# robot.net
KiCad netlist of a schematic drawn in EAGLE
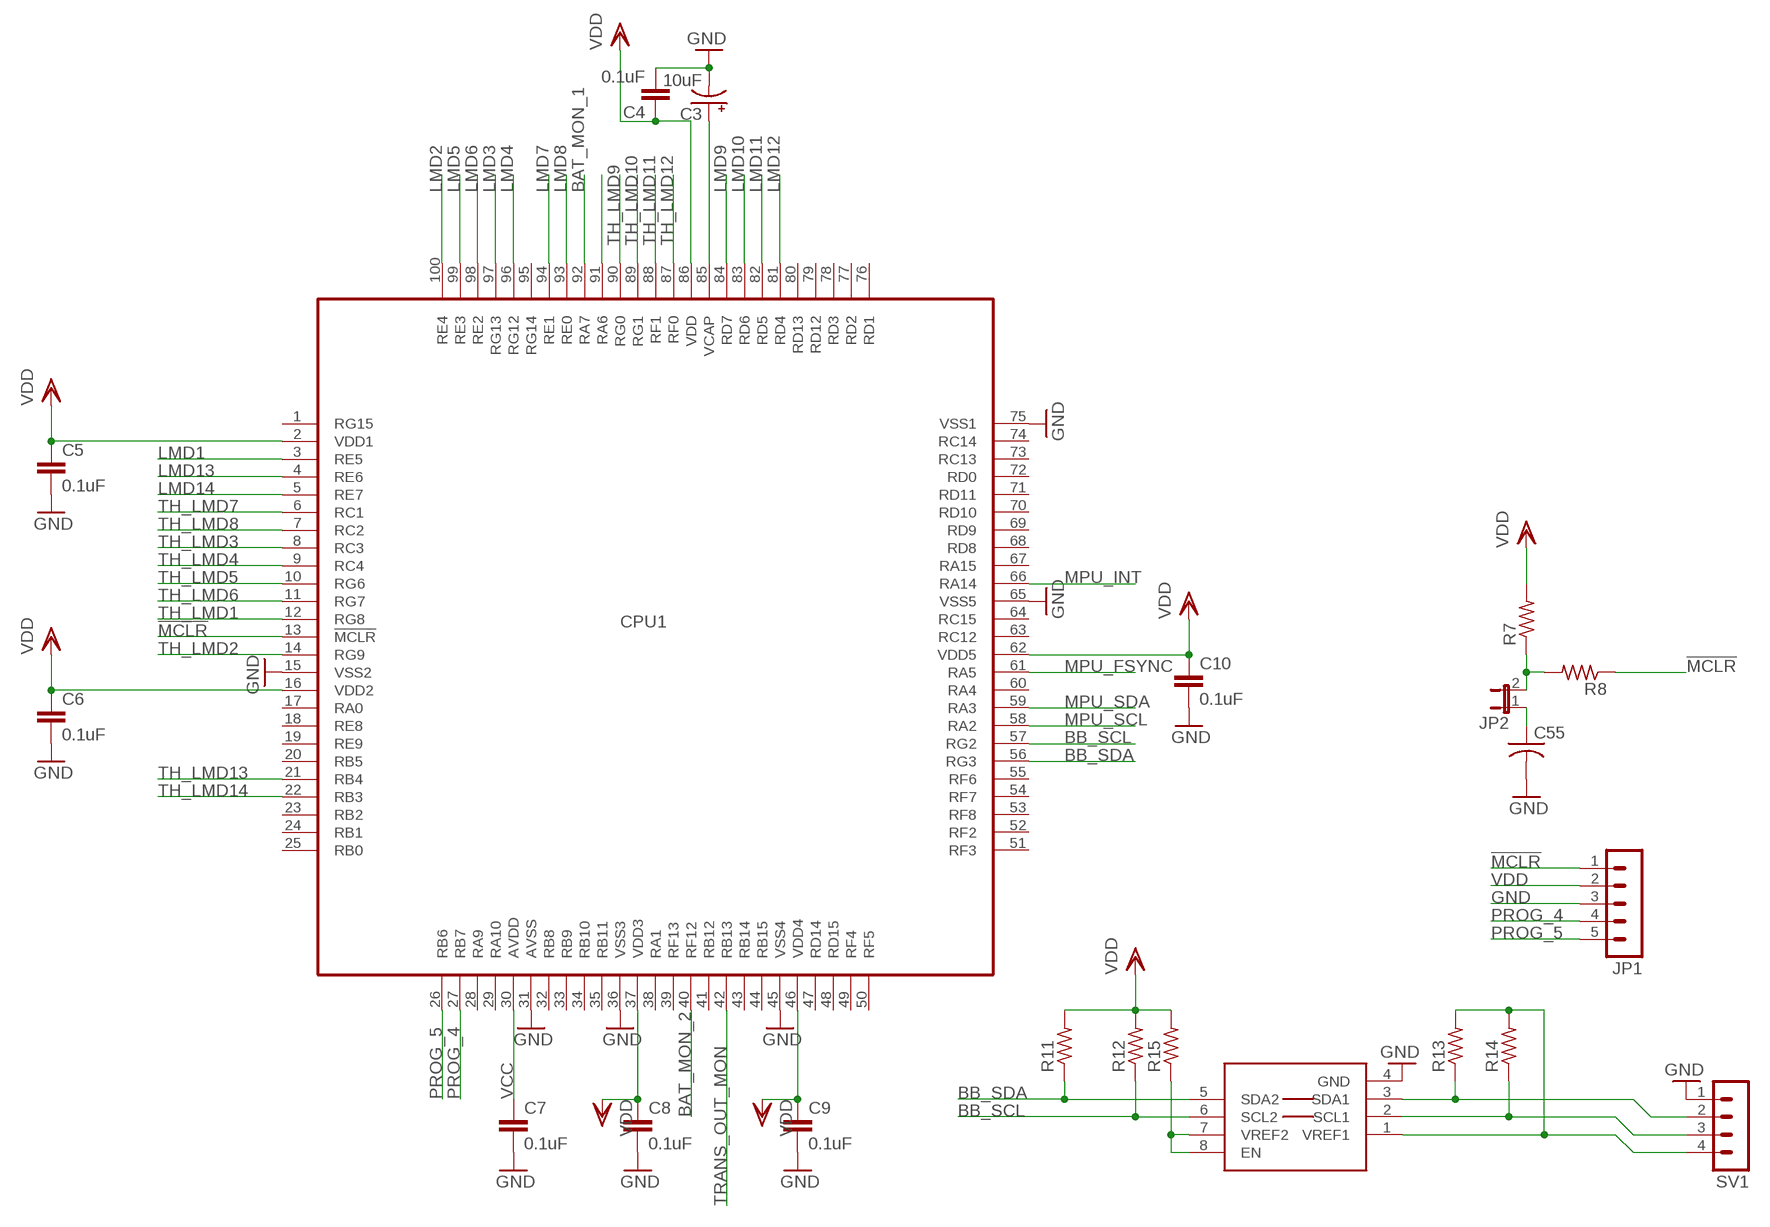
[diagram p0: schematic, sheet 1]
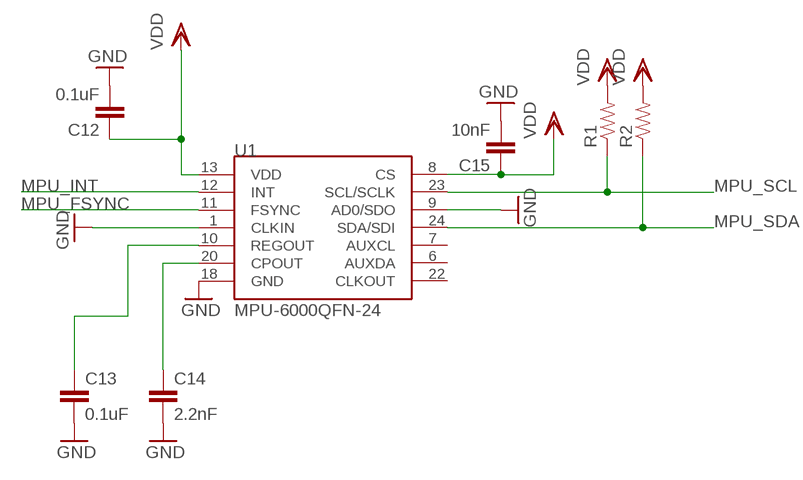
[diagram p1: schematic, sheet 2]
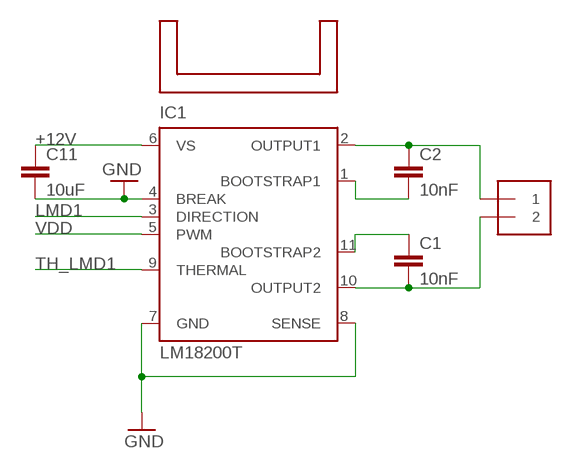
[diagram p2: schematic, sheet 3]
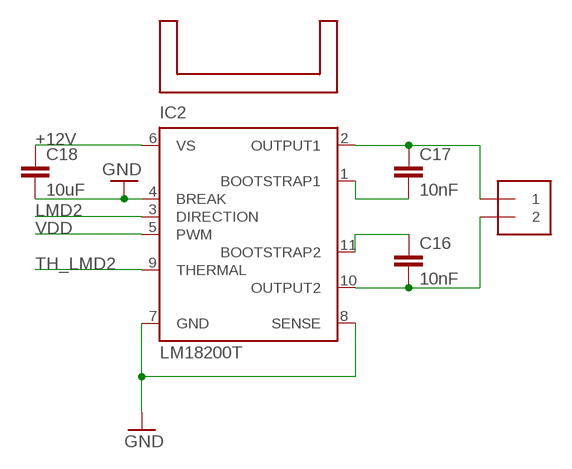
[diagram p3: schematic, sheet 4]
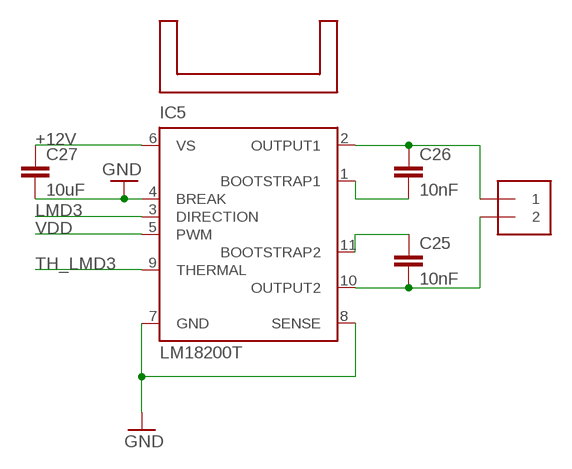
[diagram p4: schematic, sheet 5]
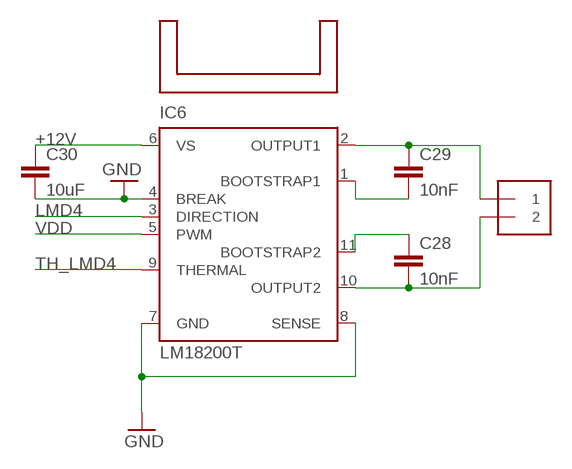
[diagram p5: schematic, sheet 6]
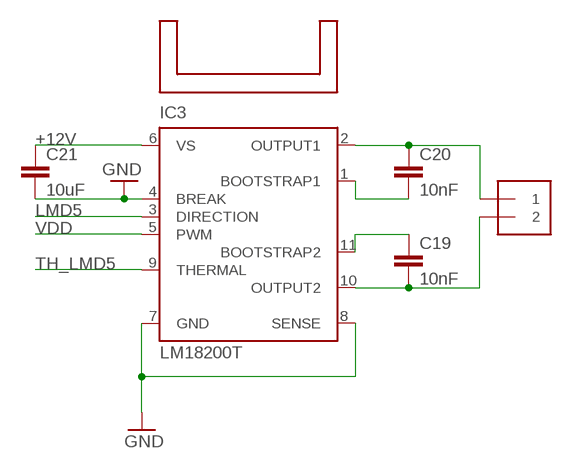
[diagram p6: schematic, sheet 7]
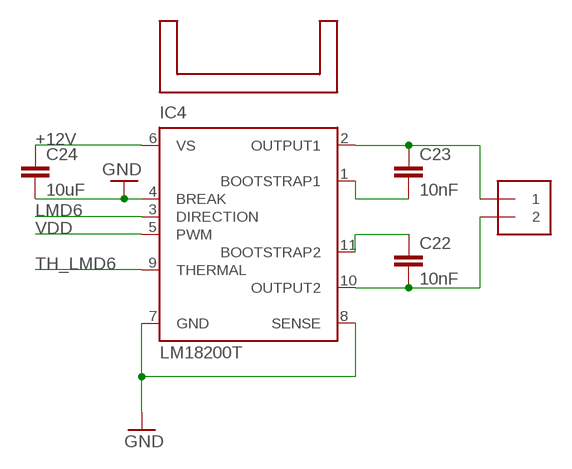
[diagram p7: schematic, sheet 8]
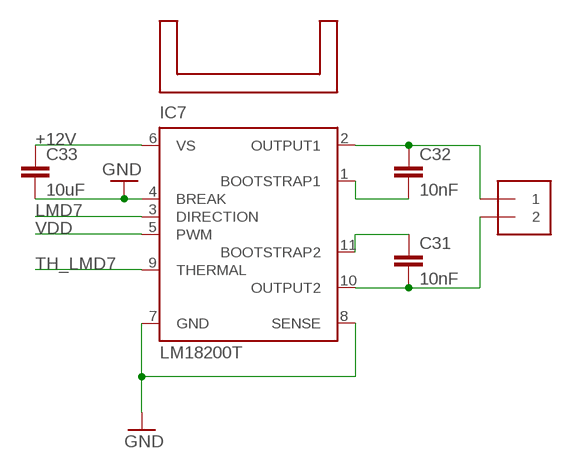
[diagram p8: schematic, sheet 9]
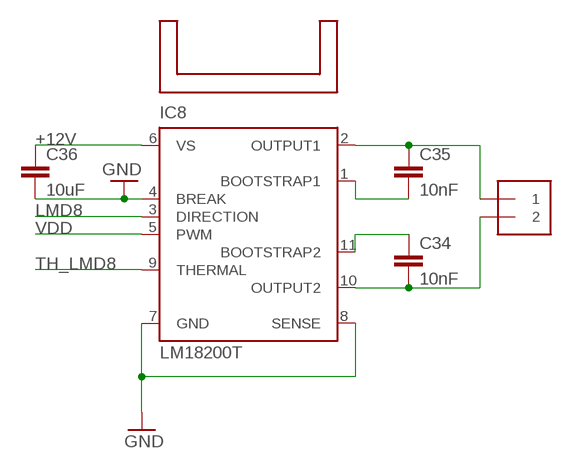
[diagram p9: schematic, sheet 10]
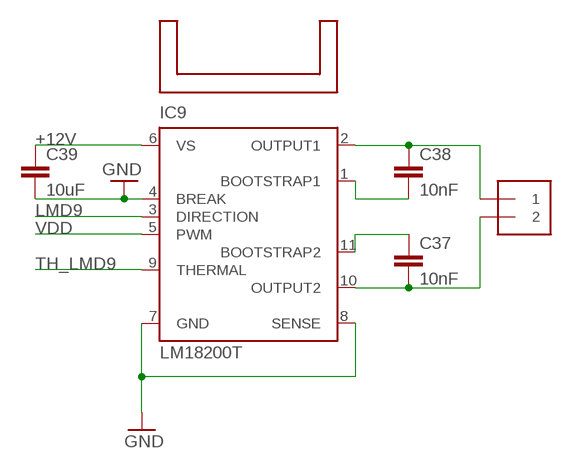
[diagram p10: schematic, sheet 11]
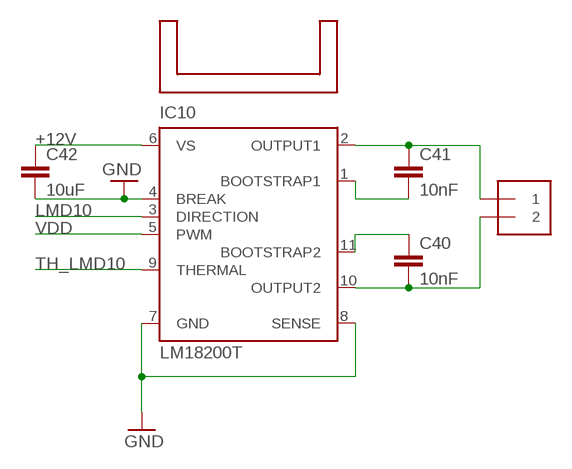
[diagram p11: schematic, sheet 12]
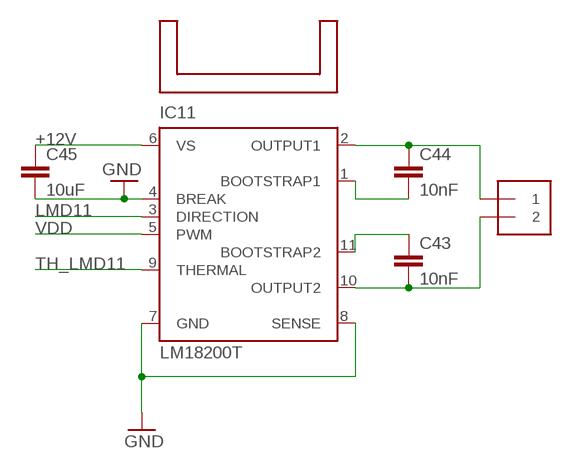
[diagram p12: schematic, sheet 13]
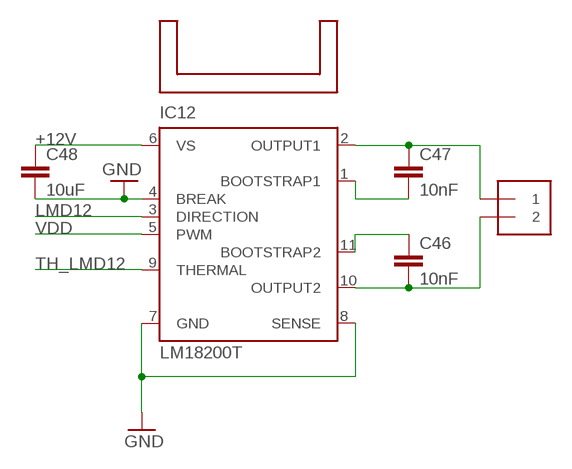
[diagram p13: schematic, sheet 14]
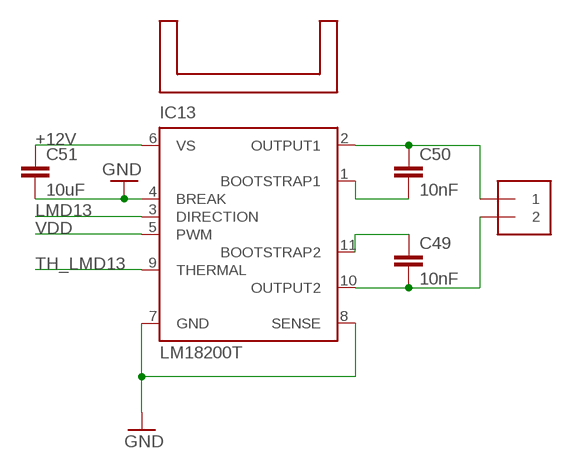
[diagram p14: schematic, sheet 15]
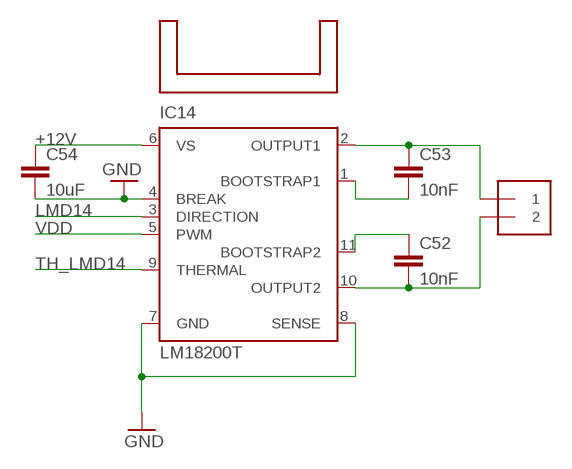
[diagram p15: schematic, sheet 16]
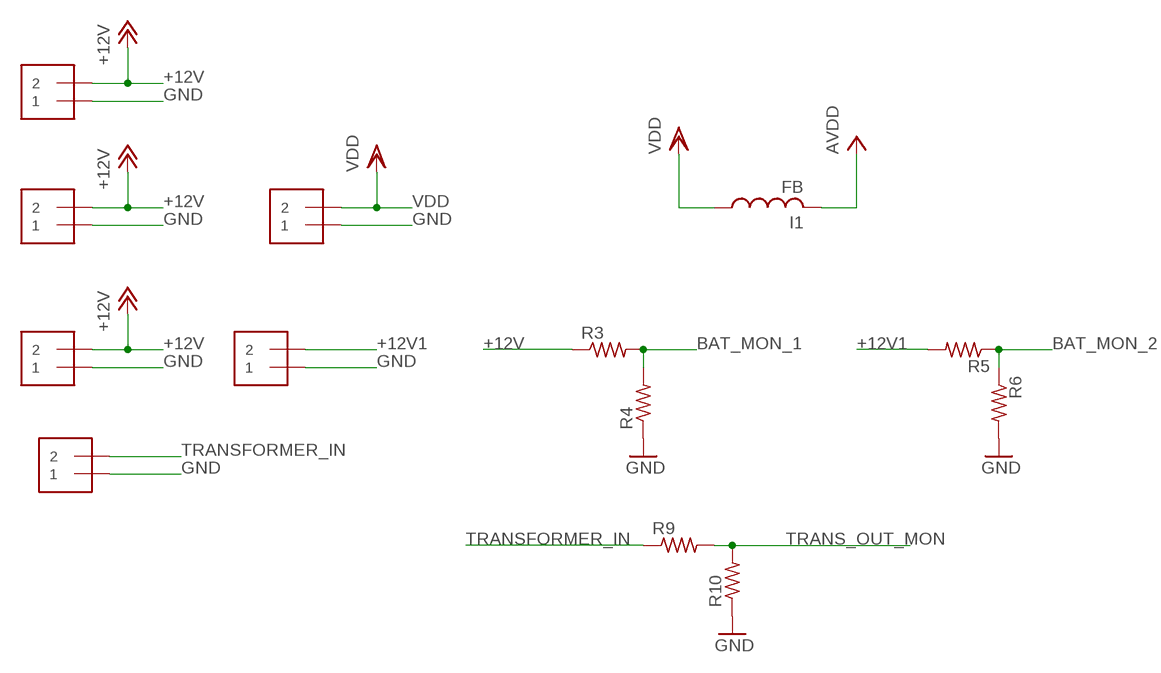
[diagram p16: schematic, sheet 17]

(export (version "E")
  (design (tool "Eeschema 10.0.6"))
  (components
    (comp (ref "C28")
      (value "10nF")
      (footprint "eagle-import:0402-CAP")
      (libsource (lib "eagle-import") (part "10NF-CER"))
    )
    (comp (ref "C29")
      (value "10nF")
      (footprint "eagle-import:0402-CAP")
      (libsource (lib "eagle-import") (part "10NF-CER"))
    )
    (comp (ref "C30")
      (value "10uF")
      (footprint "eagle-import:1206")
      (libsource (lib "eagle-import") (part "10UF-6.3V-20%(1206)"))
    )
    (comp (ref "IC6")
      (value "LM18200T")
      (footprint "eagle-import:TO-220-11")
      (libsource (lib "eagle-import") (part "LM18200T"))
    )
    (comp (ref "J6")
      (value "1X2-3.5MM")
      (footprint "eagle-import:1X2-3.5MM")
      (libsource (lib "eagle-import") (part "1X2-3.5MM"))
    )
    (comp (ref "U$6")
      (value "593002B03400G")
      (footprint "eagle-import:593002B03400G")
      (libsource (lib "eagle-import") (part "593002B03400G"))
    )
    (comp (ref "C12")
      (value "0.1uF")
      (footprint "eagle-import:0402-CAP")
      (libsource (lib "eagle-import") (part "0.1UF-25V(+80/-20%)(0603)"))
    )
    (comp (ref "C13")
      (value "0.1uF")
      (footprint "eagle-import:0402-CAP")
      (libsource (lib "eagle-import") (part "0.1UF-25V(+80/-20%)(0603)"))
    )
    (comp (ref "C14")
      (value "2.2nF")
      (footprint "eagle-import:0402-CAP")
      (libsource (lib "eagle-import") (part "10NF-CER"))
    )
    (comp (ref "C15")
      (value "10nF")
      (footprint "eagle-import:0402-CAP")
      (libsource (lib "eagle-import") (part "10NF-CER"))
    )
    (comp (ref "R1")
      (value "RESISTOR0603-RES")
      (footprint "eagle-import:0603-RES")
      (libsource (lib "eagle-import") (part "RESISTOR0603-RES"))
    )
    (comp (ref "R2")
      (value "RESISTOR0603-RES")
      (footprint "eagle-import:0603-RES")
      (libsource (lib "eagle-import") (part "RESISTOR0603-RES"))
    )
    (comp (ref "U1")
      (value "MPU-6000QFN-24")
      (footprint "eagle-import:QFN-24-TESTING")
      (libsource (lib "eagle-import") (part "MPU-6000QFN-24"))
    )
    (comp (ref "C1")
      (value "10nF")
      (footprint "eagle-import:0402-CAP")
      (libsource (lib "eagle-import") (part "10NF-CER"))
    )
    (comp (ref "C2")
      (value "10nF")
      (footprint "eagle-import:0402-CAP")
      (libsource (lib "eagle-import") (part "10NF-CER"))
    )
    (comp (ref "C11")
      (value "10uF")
      (footprint "eagle-import:1206")
      (libsource (lib "eagle-import") (part "10UF-6.3V-20%(1206)"))
    )
    (comp (ref "IC1")
      (value "LM18200T")
      (footprint "eagle-import:TO-220-11")
      (libsource (lib "eagle-import") (part "LM18200T"))
    )
    (comp (ref "J13")
      (value "1X2-3.5MM")
      (footprint "eagle-import:1X2-3.5MM")
      (libsource (lib "eagle-import") (part "1X2-3.5MM"))
    )
    (comp (ref "U$3")
      (value "593002B03400G")
      (footprint "eagle-import:593002B03400G")
      (libsource (lib "eagle-import") (part "593002B03400G"))
    )
    (comp (ref "C40")
      (value "10nF")
      (footprint "eagle-import:0402-CAP")
      (libsource (lib "eagle-import") (part "10NF-CER"))
    )
    (comp (ref "C41")
      (value "10nF")
      (footprint "eagle-import:0402-CAP")
      (libsource (lib "eagle-import") (part "10NF-CER"))
    )
    (comp (ref "C42")
      (value "10uF")
      (footprint "eagle-import:1206")
      (libsource (lib "eagle-import") (part "10UF-6.3V-20%(1206)"))
    )
    (comp (ref "IC10")
      (value "LM18200T")
      (footprint "eagle-import:TO-220-11")
      (libsource (lib "eagle-import") (part "LM18200T"))
    )
    (comp (ref "J10")
      (value "1X2-3.5MM")
      (footprint "eagle-import:1X2-3.5MM")
      (libsource (lib "eagle-import") (part "1X2-3.5MM"))
    )
    (comp (ref "U$12")
      (value "593002B03400G")
      (footprint "eagle-import:593002B03400G")
      (libsource (lib "eagle-import") (part "593002B03400G"))
    )
    (comp (ref "C22")
      (value "10nF")
      (footprint "eagle-import:0402-CAP")
      (libsource (lib "eagle-import") (part "10NF-CER"))
    )
    (comp (ref "C23")
      (value "10nF")
      (footprint "eagle-import:0402-CAP")
      (libsource (lib "eagle-import") (part "10NF-CER"))
    )
    (comp (ref "C24")
      (value "10uF")
      (footprint "eagle-import:1206")
      (libsource (lib "eagle-import") (part "10UF-6.3V-20%(1206)"))
    )
    (comp (ref "IC4")
      (value "LM18200T")
      (footprint "eagle-import:TO-220-11")
      (libsource (lib "eagle-import") (part "LM18200T"))
    )
    (comp (ref "J4")
      (value "1X2-3.5MM")
      (footprint "eagle-import:1X2-3.5MM")
      (libsource (lib "eagle-import") (part "1X2-3.5MM"))
    )
    (comp (ref "U$8")
      (value "593002B03400G")
      (footprint "eagle-import:593002B03400G")
      (libsource (lib "eagle-import") (part "593002B03400G"))
    )
    (comp (ref "C49")
      (value "10nF")
      (footprint "eagle-import:0402-CAP")
      (libsource (lib "eagle-import") (part "10NF-CER"))
    )
    (comp (ref "C50")
      (value "10nF")
      (footprint "eagle-import:0402-CAP")
      (libsource (lib "eagle-import") (part "10NF-CER"))
    )
    (comp (ref "C51")
      (value "10uF")
      (footprint "eagle-import:1206")
      (libsource (lib "eagle-import") (part "10UF-6.3V-20%(1206)"))
    )
    (comp (ref "IC13")
      (value "LM18200T")
      (footprint "eagle-import:TO-220-11")
      (libsource (lib "eagle-import") (part "LM18200T"))
    )
    (comp (ref "J15")
      (value "1X2-3.5MM")
      (footprint "eagle-import:1X2-3.5MM")
      (libsource (lib "eagle-import") (part "1X2-3.5MM"))
    )
    (comp (ref "U$15")
      (value "593002B03400G")
      (footprint "eagle-import:593002B03400G")
      (libsource (lib "eagle-import") (part "593002B03400G"))
    )
    (comp (ref "C19")
      (value "10nF")
      (footprint "eagle-import:0402-CAP")
      (libsource (lib "eagle-import") (part "10NF-CER"))
    )
    (comp (ref "C20")
      (value "10nF")
      (footprint "eagle-import:0402-CAP")
      (libsource (lib "eagle-import") (part "10NF-CER"))
    )
    (comp (ref "C21")
      (value "10uF")
      (footprint "eagle-import:1206")
      (libsource (lib "eagle-import") (part "10UF-6.3V-20%(1206)"))
    )
    (comp (ref "IC3")
      (value "LM18200T")
      (footprint "eagle-import:TO-220-11")
      (libsource (lib "eagle-import") (part "LM18200T"))
    )
    (comp (ref "J3")
      (value "1X2-3.5MM")
      (footprint "eagle-import:1X2-3.5MM")
      (libsource (lib "eagle-import") (part "1X2-3.5MM"))
    )
    (comp (ref "U$7")
      (value "593002B03400G")
      (footprint "eagle-import:593002B03400G")
      (libsource (lib "eagle-import") (part "593002B03400G"))
    )
    (comp (ref "C31")
      (value "10nF")
      (footprint "eagle-import:0402-CAP")
      (libsource (lib "eagle-import") (part "10NF-CER"))
    )
    (comp (ref "C32")
      (value "10nF")
      (footprint "eagle-import:0402-CAP")
      (libsource (lib "eagle-import") (part "10NF-CER"))
    )
    (comp (ref "C33")
      (value "10uF")
      (footprint "eagle-import:1206")
      (libsource (lib "eagle-import") (part "10UF-6.3V-20%(1206)"))
    )
    (comp (ref "IC7")
      (value "LM18200T")
      (footprint "eagle-import:TO-220-11")
      (libsource (lib "eagle-import") (part "LM18200T"))
    )
    (comp (ref "J7")
      (value "1X2-3.5MM")
      (footprint "eagle-import:1X2-3.5MM")
      (libsource (lib "eagle-import") (part "1X2-3.5MM"))
    )
    (comp (ref "U$9")
      (value "593002B03400G")
      (footprint "eagle-import:593002B03400G")
      (libsource (lib "eagle-import") (part "593002B03400G"))
    )
    (comp (ref "C25")
      (value "10nF")
      (footprint "eagle-import:0402-CAP")
      (libsource (lib "eagle-import") (part "10NF-CER"))
    )
    (comp (ref "C26")
      (value "10nF")
      (footprint "eagle-import:0402-CAP")
      (libsource (lib "eagle-import") (part "10NF-CER"))
    )
    (comp (ref "C27")
      (value "10uF")
      (footprint "eagle-import:1206")
      (libsource (lib "eagle-import") (part "10UF-6.3V-20%(1206)"))
    )
    (comp (ref "IC5")
      (value "LM18200T")
      (footprint "eagle-import:TO-220-11")
      (libsource (lib "eagle-import") (part "LM18200T"))
    )
    (comp (ref "J5")
      (value "1X2-3.5MM")
      (footprint "eagle-import:1X2-3.5MM")
      (libsource (lib "eagle-import") (part "1X2-3.5MM"))
    )
    (comp (ref "U$5")
      (value "593002B03400G")
      (footprint "eagle-import:593002B03400G")
      (libsource (lib "eagle-import") (part "593002B03400G"))
    )
    (comp (ref "C16")
      (value "10nF")
      (footprint "eagle-import:0402-CAP")
      (libsource (lib "eagle-import") (part "10NF-CER"))
    )
    (comp (ref "C17")
      (value "10nF")
      (footprint "eagle-import:0402-CAP")
      (libsource (lib "eagle-import") (part "10NF-CER"))
    )
    (comp (ref "C18")
      (value "10uF")
      (footprint "eagle-import:1206")
      (libsource (lib "eagle-import") (part "10UF-6.3V-20%(1206)"))
    )
    (comp (ref "IC2")
      (value "LM18200T")
      (footprint "eagle-import:TO-220-11")
      (libsource (lib "eagle-import") (part "LM18200T"))
    )
    (comp (ref "J2")
      (value "1X2-3.5MM")
      (footprint "eagle-import:1X2-3.5MM")
      (libsource (lib "eagle-import") (part "1X2-3.5MM"))
    )
    (comp (ref "U$4")
      (value "593002B03400G")
      (footprint "eagle-import:593002B03400G")
      (libsource (lib "eagle-import") (part "593002B03400G"))
    )
    (comp (ref "C37")
      (value "10nF")
      (footprint "eagle-import:0402-CAP")
      (libsource (lib "eagle-import") (part "10NF-CER"))
    )
    (comp (ref "C38")
      (value "10nF")
      (footprint "eagle-import:0402-CAP")
      (libsource (lib "eagle-import") (part "10NF-CER"))
    )
    (comp (ref "C39")
      (value "10uF")
      (footprint "eagle-import:1206")
      (libsource (lib "eagle-import") (part "10UF-6.3V-20%(1206)"))
    )
    (comp (ref "IC9")
      (value "LM18200T")
      (footprint "eagle-import:TO-220-11")
      (libsource (lib "eagle-import") (part "LM18200T"))
    )
    (comp (ref "J9")
      (value "1X2-3.5MM")
      (footprint "eagle-import:1X2-3.5MM")
      (libsource (lib "eagle-import") (part "1X2-3.5MM"))
    )
    (comp (ref "U$11")
      (value "593002B03400G")
      (footprint "eagle-import:593002B03400G")
      (libsource (lib "eagle-import") (part "593002B03400G"))
    )
    (comp (ref "C52")
      (value "10nF")
      (footprint "eagle-import:0402-CAP")
      (libsource (lib "eagle-import") (part "10NF-CER"))
    )
    (comp (ref "C53")
      (value "10nF")
      (footprint "eagle-import:0402-CAP")
      (libsource (lib "eagle-import") (part "10NF-CER"))
    )
    (comp (ref "C54")
      (value "10uF")
      (footprint "eagle-import:1206")
      (libsource (lib "eagle-import") (part "10UF-6.3V-20%(1206)"))
    )
    (comp (ref "IC14")
      (value "LM18200T")
      (footprint "eagle-import:TO-220-11")
      (libsource (lib "eagle-import") (part "LM18200T"))
    )
    (comp (ref "J16")
      (value "1X2-3.5MM")
      (footprint "eagle-import:1X2-3.5MM")
      (libsource (lib "eagle-import") (part "1X2-3.5MM"))
    )
    (comp (ref "U$16")
      (value "593002B03400G")
      (footprint "eagle-import:593002B03400G")
      (libsource (lib "eagle-import") (part "593002B03400G"))
    )
    (comp (ref "I1") (value "FB") (footprint "eagle-import:FB") (libsource (lib "eagle-import") (part "FB")))
    (comp (ref "J1")
      (value "1X2-3.5MM")
      (footprint "eagle-import:1X2-3.5MM")
      (libsource (lib "eagle-import") (part "1X2-3.5MM"))
    )
    (comp (ref "J12")
      (value "1X2-3.5MM")
      (footprint "eagle-import:1X2-3.5MM")
      (libsource (lib "eagle-import") (part "1X2-3.5MM"))
    )
    (comp (ref "J17")
      (value "1X2-3.5MM")
      (footprint "eagle-import:1X2-3.5MM")
      (libsource (lib "eagle-import") (part "1X2-3.5MM"))
    )
    (comp (ref "J18")
      (value "1X2-3.5MM")
      (footprint "eagle-import:1X2-3.5MM")
      (libsource (lib "eagle-import") (part "1X2-3.5MM"))
    )
    (comp (ref "J19")
      (value "1X2-3.5MM")
      (footprint "eagle-import:1X2-3.5MM")
      (libsource (lib "eagle-import") (part "1X2-3.5MM"))
    )
    (comp (ref "J20")
      (value "1X2-3.5MM")
      (footprint "eagle-import:1X2-3.5MM")
      (libsource (lib "eagle-import") (part "1X2-3.5MM"))
    )
    (comp (ref "R3")
      (value "R-US_R0603")
      (footprint "eagle-import:R0603")
      (libsource (lib "eagle-import") (part "R-US_R0603"))
    )
    (comp (ref "R4")
      (value "R-US_R0603")
      (footprint "eagle-import:R0603")
      (libsource (lib "eagle-import") (part "R-US_R0603"))
    )
    (comp (ref "R5")
      (value "R-US_R0603")
      (footprint "eagle-import:R0603")
      (libsource (lib "eagle-import") (part "R-US_R0603"))
    )
    (comp (ref "R6")
      (value "R-US_R0603")
      (footprint "eagle-import:R0603")
      (libsource (lib "eagle-import") (part "R-US_R0603"))
    )
    (comp (ref "R9")
      (value "R-US_R0603")
      (footprint "eagle-import:R0603")
      (libsource (lib "eagle-import") (part "R-US_R0603"))
    )
    (comp (ref "R10")
      (value "R-US_R0603")
      (footprint "eagle-import:R0603")
      (libsource (lib "eagle-import") (part "R-US_R0603"))
    )
    (comp (ref "C43")
      (value "10nF")
      (footprint "eagle-import:0402-CAP")
      (libsource (lib "eagle-import") (part "10NF-CER"))
    )
    (comp (ref "C44")
      (value "10nF")
      (footprint "eagle-import:0402-CAP")
      (libsource (lib "eagle-import") (part "10NF-CER"))
    )
    (comp (ref "C45")
      (value "10uF")
      (footprint "eagle-import:1206")
      (libsource (lib "eagle-import") (part "10UF-6.3V-20%(1206)"))
    )
    (comp (ref "IC11")
      (value "LM18200T")
      (footprint "eagle-import:TO-220-11")
      (libsource (lib "eagle-import") (part "LM18200T"))
    )
    (comp (ref "J11")
      (value "1X2-3.5MM")
      (footprint "eagle-import:1X2-3.5MM")
      (libsource (lib "eagle-import") (part "1X2-3.5MM"))
    )
    (comp (ref "U$13")
      (value "593002B03400G")
      (footprint "eagle-import:593002B03400G")
      (libsource (lib "eagle-import") (part "593002B03400G"))
    )
    (comp (ref "C34")
      (value "10nF")
      (footprint "eagle-import:0402-CAP")
      (libsource (lib "eagle-import") (part "10NF-CER"))
    )
    (comp (ref "C35")
      (value "10nF")
      (footprint "eagle-import:0402-CAP")
      (libsource (lib "eagle-import") (part "10NF-CER"))
    )
    (comp (ref "C36")
      (value "10uF")
      (footprint "eagle-import:1206")
      (libsource (lib "eagle-import") (part "10UF-6.3V-20%(1206)"))
    )
    (comp (ref "IC8")
      (value "LM18200T")
      (footprint "eagle-import:TO-220-11")
      (libsource (lib "eagle-import") (part "LM18200T"))
    )
    (comp (ref "J8")
      (value "1X2-3.5MM")
      (footprint "eagle-import:1X2-3.5MM")
      (libsource (lib "eagle-import") (part "1X2-3.5MM"))
    )
    (comp (ref "U$10")
      (value "593002B03400G")
      (footprint "eagle-import:593002B03400G")
      (libsource (lib "eagle-import") (part "593002B03400G"))
    )
    (comp (ref "C46")
      (value "10nF")
      (footprint "eagle-import:0402-CAP")
      (libsource (lib "eagle-import") (part "10NF-CER"))
    )
    (comp (ref "C47")
      (value "10nF")
      (footprint "eagle-import:0402-CAP")
      (libsource (lib "eagle-import") (part "10NF-CER"))
    )
    (comp (ref "C48")
      (value "10uF")
      (footprint "eagle-import:1206")
      (libsource (lib "eagle-import") (part "10UF-6.3V-20%(1206)"))
    )
    (comp (ref "IC12")
      (value "LM18200T")
      (footprint "eagle-import:TO-220-11")
      (libsource (lib "eagle-import") (part "LM18200T"))
    )
    (comp (ref "J14")
      (value "1X2-3.5MM")
      (footprint "eagle-import:1X2-3.5MM")
      (libsource (lib "eagle-import") (part "1X2-3.5MM"))
    )
    (comp (ref "U$14")
      (value "593002B03400G")
      (footprint "eagle-import:593002B03400G")
      (libsource (lib "eagle-import") (part "593002B03400G"))
    )
    (comp (ref "C3")
      (value "10uF")
      (footprint "eagle-import:EIA3216")
      (libsource (lib "eagle-import") (part "10UF-TANT"))
    )
    (comp (ref "C4")
      (value "0.1uF")
      (footprint "eagle-import:0402-CAP")
      (libsource (lib "eagle-import") (part "0.1UF-25V(+80/-20%)(0603)"))
    )
    (comp (ref "C5")
      (value "0.1uF")
      (footprint "eagle-import:0402-CAP")
      (libsource (lib "eagle-import") (part "0.1UF-25V(+80/-20%)(0603)"))
    )
    (comp (ref "C6")
      (value "0.1uF")
      (footprint "eagle-import:0402-CAP")
      (libsource (lib "eagle-import") (part "0.1UF-25V(+80/-20%)(0603)"))
    )
    (comp (ref "C7")
      (value "0.1uF")
      (footprint "eagle-import:0402-CAP")
      (libsource (lib "eagle-import") (part "0.1UF-25V(+80/-20%)(0603)"))
    )
    (comp (ref "C8")
      (value "0.1uF")
      (footprint "eagle-import:0402-CAP")
      (libsource (lib "eagle-import") (part "0.1UF-25V(+80/-20%)(0603)"))
    )
    (comp (ref "C9")
      (value "0.1uF")
      (footprint "eagle-import:0402-CAP")
      (libsource (lib "eagle-import") (part "0.1UF-25V(+80/-20%)(0603)"))
    )
    (comp (ref "C10")
      (value "0.1uF")
      (footprint "eagle-import:0402-CAP")
      (libsource (lib "eagle-import") (part "0.1UF-25V(+80/-20%)(0603)"))
    )
    (comp (ref "C55")
      (value "C-USC0603")
      (footprint "eagle-import:C0603")
      (libsource (lib "eagle-import") (part "C-USC0603"))
    )
    (comp (ref "CPU1")
      (value "DSPIC33FJ32GS610TQFP")
      (footprint "eagle-import:TQFP100-14X14")
      (libsource (lib "eagle-import") (part "DSPIC33FJ32GS610TQFP"))
    )
    (comp (ref "JP1")
      (value "MA05-1")
      (footprint "eagle-import:MA05-1")
      (libsource (lib "eagle-import") (part "MA05-1"))
    )
    (comp (ref "JP2")
      (value "JP1E")
      (footprint "eagle-import:JP1")
      (libsource (lib "eagle-import") (part "JP1E"))
    )
    (comp (ref "R7")
      (value "R-US_R0603")
      (footprint "eagle-import:R0603")
      (libsource (lib "eagle-import") (part "R-US_R0603"))
    )
    (comp (ref "R8")
      (value "R-US_R0603")
      (footprint "eagle-import:R0603")
      (libsource (lib "eagle-import") (part "R-US_R0603"))
    )
    (comp (ref "R11")
      (value "R-US_R0603")
      (footprint "eagle-import:R0603")
      (libsource (lib "eagle-import") (part "R-US_R0603"))
    )
    (comp (ref "R12")
      (value "R-US_R0603")
      (footprint "eagle-import:R0603")
      (libsource (lib "eagle-import") (part "R-US_R0603"))
    )
    (comp (ref "R13")
      (value "R-US_R0603")
      (footprint "eagle-import:R0603")
      (libsource (lib "eagle-import") (part "R-US_R0603"))
    )
    (comp (ref "R14")
      (value "R-US_R0603")
      (footprint "eagle-import:R0603")
      (libsource (lib "eagle-import") (part "R-US_R0603"))
    )
    (comp (ref "R15")
      (value "R-US_R0603")
      (footprint "eagle-import:R0603")
      (libsource (lib "eagle-import") (part "R-US_R0603"))
    )
    (comp (ref "SV1")
      (value "MA04-1")
      (footprint "eagle-import:MA04-1")
      (libsource (lib "eagle-import") (part "MA04-1"))
    )
    (comp (ref "U$17")
      (value "PCA9306")
      (footprint "eagle-import:PSOP-8")
      (libsource (lib "eagle-import") (part "PCA9306"))
    )
  )
  (nets
    (net (code "1") (name "+12V") (class "Default")
      (node (ref "C11") (pin "1") (pinfunction "1_1") (pintype "passive"))
      (node (ref "C18") (pin "1") (pinfunction "1_1") (pintype "passive"))
      (node (ref "C21") (pin "1") (pinfunction "1_1") (pintype "passive"))
      (node (ref "C24") (pin "1") (pinfunction "1_1") (pintype "passive"))
      (node (ref "C27") (pin "1") (pinfunction "1_1") (pintype "passive"))
      (node (ref "C30") (pin "1") (pinfunction "1_1") (pintype "passive"))
      (node (ref "C33") (pin "1") (pinfunction "1_1") (pintype "passive"))
      (node (ref "C36") (pin "1") (pinfunction "1_1") (pintype "passive"))
      (node (ref "C39") (pin "1") (pinfunction "1_1") (pintype "passive"))
      (node (ref "C42") (pin "1") (pinfunction "1_1") (pintype "passive"))
      (node (ref "C45") (pin "1") (pinfunction "1_1") (pintype "passive"))
      (node (ref "C48") (pin "1") (pinfunction "1_1") (pintype "passive"))
      (node (ref "C51") (pin "1") (pinfunction "1_1") (pintype "passive"))
      (node (ref "C54") (pin "1") (pinfunction "1_1") (pintype "passive"))
      (node (ref "IC1") (pin "6") (pinfunction "VS_6") (pintype "power_in"))
      (node (ref "IC10") (pin "6") (pinfunction "VS_6") (pintype "power_in"))
      (node (ref "IC11") (pin "6") (pinfunction "VS_6") (pintype "power_in"))
      (node (ref "IC12") (pin "6") (pinfunction "VS_6") (pintype "power_in"))
      (node (ref "IC13") (pin "6") (pinfunction "VS_6") (pintype "power_in"))
      (node (ref "IC14") (pin "6") (pinfunction "VS_6") (pintype "power_in"))
      (node (ref "IC2") (pin "6") (pinfunction "VS_6") (pintype "power_in"))
      (node (ref "IC3") (pin "6") (pinfunction "VS_6") (pintype "power_in"))
      (node (ref "IC4") (pin "6") (pinfunction "VS_6") (pintype "power_in"))
      (node (ref "IC5") (pin "6") (pinfunction "VS_6") (pintype "power_in"))
      (node (ref "IC6") (pin "6") (pinfunction "VS_6") (pintype "power_in"))
      (node (ref "IC7") (pin "6") (pinfunction "VS_6") (pintype "power_in"))
      (node (ref "IC8") (pin "6") (pinfunction "VS_6") (pintype "power_in"))
      (node (ref "IC9") (pin "6") (pinfunction "VS_6") (pintype "power_in"))
      (node (ref "J12") (pin "2") (pinfunction "2_2") (pintype "passive"))
      (node (ref "J17") (pin "2") (pinfunction "2_2") (pintype "passive"))
      (node (ref "J20") (pin "2") (pinfunction "2_2") (pintype "passive"))
      (node (ref "R3") (pin "1") (pinfunction "1_1") (pintype "passive"))
    )
    (net (code "2") (name "+12V1") (class "Default")
      (node (ref "J18") (pin "2") (pinfunction "2_2") (pintype "passive"))
      (node (ref "R5") (pin "2") (pinfunction "2_2") (pintype "passive"))
    )
    (net (code "3") (name "BAT_MON_1") (class "Default")
      (node (ref "CPU1") (pin "92") (pinfunction "RA7_92") (pintype "bidirectional"))
      (node (ref "R3") (pin "2") (pinfunction "2_2") (pintype "passive"))
      (node (ref "R4") (pin "2") (pinfunction "2_2") (pintype "passive"))
    )
    (net (code "4") (name "BAT_MON_2") (class "Default")
      (node (ref "CPU1") (pin "40") (pinfunction "RF12_40") (pintype "bidirectional"))
      (node (ref "R5") (pin "1") (pinfunction "1_1") (pintype "passive"))
      (node (ref "R6") (pin "1") (pinfunction "1_1") (pintype "passive"))
    )
    (net (code "5") (name "BB_SCL") (class "Default")
      (node (ref "CPU1") (pin "57") (pinfunction "RG2_57") (pintype "bidirectional"))
      (node (ref "R12") (pin "1") (pinfunction "1_1") (pintype "passive"))
      (node (ref "U$17") (pin "6") (pinfunction "SCL2_6") (pintype "bidirectional"))
    )
    (net (code "6") (name "BB_SDA") (class "Default")
      (node (ref "CPU1") (pin "56") (pinfunction "RG3_56") (pintype "bidirectional"))
      (node (ref "R11") (pin "1") (pinfunction "1_1") (pintype "passive"))
      (node (ref "U$17") (pin "5") (pinfunction "SDA2_5") (pintype "bidirectional"))
    )
    (net (code "7") (name "GND") (class "Default")
      (node (ref "C10") (pin "2") (pinfunction "2_2") (pintype "passive"))
      (node (ref "C11") (pin "2") (pinfunction "2_2") (pintype "passive"))
      (node (ref "C12") (pin "2") (pinfunction "2_2") (pintype "passive"))
      (node (ref "C13") (pin "2") (pinfunction "2_2") (pintype "passive"))
      (node (ref "C14") (pin "2") (pinfunction "2_2") (pintype "passive"))
      (node (ref "C15") (pin "2") (pinfunction "2_2") (pintype "passive"))
      (node (ref "C18") (pin "2") (pinfunction "2_2") (pintype "passive"))
      (node (ref "C21") (pin "2") (pinfunction "2_2") (pintype "passive"))
      (node (ref "C24") (pin "2") (pinfunction "2_2") (pintype "passive"))
      (node (ref "C27") (pin "2") (pinfunction "2_2") (pintype "passive"))
      (node (ref "C3") (pin "C") (pinfunction "-_C") (pintype "passive"))
      (node (ref "C30") (pin "2") (pinfunction "2_2") (pintype "passive"))
      (node (ref "C33") (pin "2") (pinfunction "2_2") (pintype "passive"))
      (node (ref "C36") (pin "2") (pinfunction "2_2") (pintype "passive"))
      (node (ref "C39") (pin "2") (pinfunction "2_2") (pintype "passive"))
      (node (ref "C4") (pin "2") (pinfunction "2_2") (pintype "passive"))
      (node (ref "C42") (pin "2") (pinfunction "2_2") (pintype "passive"))
      (node (ref "C45") (pin "2") (pinfunction "2_2") (pintype "passive"))
      (node (ref "C48") (pin "2") (pinfunction "2_2") (pintype "passive"))
      (node (ref "C5") (pin "2") (pinfunction "2_2") (pintype "passive"))
      (node (ref "C51") (pin "2") (pinfunction "2_2") (pintype "passive"))
      (node (ref "C54") (pin "2") (pinfunction "2_2") (pintype "passive"))
      (node (ref "C55") (pin "2") (pinfunction "2_2") (pintype "passive"))
      (node (ref "C6") (pin "2") (pinfunction "2_2") (pintype "passive"))
      (node (ref "C7") (pin "2") (pinfunction "2_2") (pintype "passive"))
      (node (ref "C8") (pin "2") (pinfunction "2_2") (pintype "passive"))
      (node (ref "C9") (pin "2") (pinfunction "2_2") (pintype "passive"))
      (node (ref "CPU1") (pin "15") (pinfunction "VSS2_15") (pintype "power_in"))
      (node (ref "CPU1") (pin "31") (pinfunction "AVSS_31") (pintype "power_in"))
      (node (ref "CPU1") (pin "36") (pinfunction "VSS3_36") (pintype "power_in"))
      (node (ref "CPU1") (pin "45") (pinfunction "VSS4_45") (pintype "power_in"))
      (node (ref "CPU1") (pin "65") (pinfunction "VSS5_65") (pintype "power_in"))
      (node (ref "CPU1") (pin "75") (pinfunction "VSS1_75") (pintype "power_in"))
      (node (ref "IC1") (pin "4") (pinfunction "BREAK_4") (pintype "input"))
      (node (ref "IC1") (pin "7") (pinfunction "GND_7") (pintype "power_in"))
      (node (ref "IC1") (pin "8") (pinfunction "SENSE_8") (pintype "output"))
      (node (ref "IC10") (pin "4") (pinfunction "BREAK_4") (pintype "input"))
      (node (ref "IC10") (pin "7") (pinfunction "GND_7") (pintype "power_in"))
      (node (ref "IC10") (pin "8") (pinfunction "SENSE_8") (pintype "output"))
      (node (ref "IC11") (pin "4") (pinfunction "BREAK_4") (pintype "input"))
      (node (ref "IC11") (pin "7") (pinfunction "GND_7") (pintype "power_in"))
      (node (ref "IC11") (pin "8") (pinfunction "SENSE_8") (pintype "output"))
      (node (ref "IC12") (pin "4") (pinfunction "BREAK_4") (pintype "input"))
      (node (ref "IC12") (pin "7") (pinfunction "GND_7") (pintype "power_in"))
      (node (ref "IC12") (pin "8") (pinfunction "SENSE_8") (pintype "output"))
      (node (ref "IC13") (pin "4") (pinfunction "BREAK_4") (pintype "input"))
      (node (ref "IC13") (pin "7") (pinfunction "GND_7") (pintype "power_in"))
      (node (ref "IC13") (pin "8") (pinfunction "SENSE_8") (pintype "output"))
      (node (ref "IC14") (pin "4") (pinfunction "BREAK_4") (pintype "input"))
      (node (ref "IC14") (pin "7") (pinfunction "GND_7") (pintype "power_in"))
      (node (ref "IC14") (pin "8") (pinfunction "SENSE_8") (pintype "output"))
      (node (ref "IC2") (pin "4") (pinfunction "BREAK_4") (pintype "input"))
      (node (ref "IC2") (pin "7") (pinfunction "GND_7") (pintype "power_in"))
      (node (ref "IC2") (pin "8") (pinfunction "SENSE_8") (pintype "output"))
      (node (ref "IC3") (pin "4") (pinfunction "BREAK_4") (pintype "input"))
      (node (ref "IC3") (pin "7") (pinfunction "GND_7") (pintype "power_in"))
      (node (ref "IC3") (pin "8") (pinfunction "SENSE_8") (pintype "output"))
      (node (ref "IC4") (pin "4") (pinfunction "BREAK_4") (pintype "input"))
      (node (ref "IC4") (pin "7") (pinfunction "GND_7") (pintype "power_in"))
      (node (ref "IC4") (pin "8") (pinfunction "SENSE_8") (pintype "output"))
      (node (ref "IC5") (pin "4") (pinfunction "BREAK_4") (pintype "input"))
      (node (ref "IC5") (pin "7") (pinfunction "GND_7") (pintype "power_in"))
      (node (ref "IC5") (pin "8") (pinfunction "SENSE_8") (pintype "output"))
      (node (ref "IC6") (pin "4") (pinfunction "BREAK_4") (pintype "input"))
      (node (ref "IC6") (pin "7") (pinfunction "GND_7") (pintype "power_in"))
      (node (ref "IC6") (pin "8") (pinfunction "SENSE_8") (pintype "output"))
      (node (ref "IC7") (pin "4") (pinfunction "BREAK_4") (pintype "input"))
      (node (ref "IC7") (pin "7") (pinfunction "GND_7") (pintype "power_in"))
      (node (ref "IC7") (pin "8") (pinfunction "SENSE_8") (pintype "output"))
      (node (ref "IC8") (pin "4") (pinfunction "BREAK_4") (pintype "input"))
      (node (ref "IC8") (pin "7") (pinfunction "GND_7") (pintype "power_in"))
      (node (ref "IC8") (pin "8") (pinfunction "SENSE_8") (pintype "output"))
      (node (ref "IC9") (pin "4") (pinfunction "BREAK_4") (pintype "input"))
      (node (ref "IC9") (pin "7") (pinfunction "GND_7") (pintype "power_in"))
      (node (ref "IC9") (pin "8") (pinfunction "SENSE_8") (pintype "output"))
      (node (ref "J1") (pin "1") (pinfunction "1_1") (pintype "passive"))
      (node (ref "J12") (pin "1") (pinfunction "1_1") (pintype "passive"))
      (node (ref "J17") (pin "1") (pinfunction "1_1") (pintype "passive"))
      (node (ref "J18") (pin "1") (pinfunction "1_1") (pintype "passive"))
      (node (ref "J19") (pin "1") (pinfunction "1_1") (pintype "passive"))
      (node (ref "J20") (pin "1") (pinfunction "1_1") (pintype "passive"))
      (node (ref "JP1") (pin "3") (pinfunction "3_3") (pintype "passive"))
      (node (ref "R10") (pin "1") (pinfunction "1_1") (pintype "passive"))
      (node (ref "R4") (pin "1") (pinfunction "1_1") (pintype "passive"))
      (node (ref "R6") (pin "2") (pinfunction "2_2") (pintype "passive"))
      (node (ref "SV1") (pin "1") (pinfunction "1_1") (pintype "passive"))
      (node (ref "U$17") (pin "4") (pinfunction "GND_4") (pintype "bidirectional"))
      (node (ref "U1") (pin "1") (pinfunction "CLKIN_1") (pintype "bidirectional"))
      (node (ref "U1") (pin "18") (pinfunction "GND_18") (pintype "bidirectional"))
      (node (ref "U1") (pin "9") (pinfunction "AD0/SDO_9") (pintype "bidirectional"))
    )
    (net (code "8") (name "LMD1") (class "Default")
      (node (ref "CPU1") (pin "3") (pinfunction "RE5_3") (pintype "bidirectional"))
      (node (ref "IC1") (pin "3") (pinfunction "DIRECTION_3") (pintype "input"))
    )
    (net (code "9") (name "LMD2") (class "Default")
      (node (ref "CPU1") (pin "100") (pinfunction "RE4_100") (pintype "bidirectional"))
      (node (ref "IC2") (pin "3") (pinfunction "DIRECTION_3") (pintype "input"))
    )
    (net (code "10") (name "LMD3") (class "Default")
      (node (ref "CPU1") (pin "97") (pinfunction "RG13_97") (pintype "bidirectional"))
      (node (ref "IC5") (pin "3") (pinfunction "DIRECTION_3") (pintype "input"))
    )
    (net (code "11") (name "LMD4") (class "Default")
      (node (ref "CPU1") (pin "96") (pinfunction "RG12_96") (pintype "bidirectional"))
      (node (ref "IC6") (pin "3") (pinfunction "DIRECTION_3") (pintype "input"))
    )
    (net (code "12") (name "LMD5") (class "Default")
      (node (ref "CPU1") (pin "99") (pinfunction "RE3_99") (pintype "bidirectional"))
      (node (ref "IC3") (pin "3") (pinfunction "DIRECTION_3") (pintype "input"))
    )
    (net (code "13") (name "LMD6") (class "Default")
      (node (ref "CPU1") (pin "98") (pinfunction "RE2_98") (pintype "bidirectional"))
      (node (ref "IC4") (pin "3") (pinfunction "DIRECTION_3") (pintype "input"))
    )
    (net (code "14") (name "LMD7") (class "Default")
      (node (ref "CPU1") (pin "94") (pinfunction "RE1_94") (pintype "bidirectional"))
      (node (ref "IC7") (pin "3") (pinfunction "DIRECTION_3") (pintype "input"))
    )
    (net (code "15") (name "LMD8") (class "Default")
      (node (ref "CPU1") (pin "93") (pinfunction "RE0_93") (pintype "bidirectional"))
      (node (ref "IC8") (pin "3") (pinfunction "DIRECTION_3") (pintype "input"))
    )
    (net (code "16") (name "LMD9") (class "Default")
      (node (ref "CPU1") (pin "84") (pinfunction "RD7_84") (pintype "bidirectional"))
      (node (ref "IC9") (pin "3") (pinfunction "DIRECTION_3") (pintype "input"))
    )
    (net (code "17") (name "LMD10") (class "Default")
      (node (ref "CPU1") (pin "83") (pinfunction "RD6_83") (pintype "bidirectional"))
      (node (ref "IC10") (pin "3") (pinfunction "DIRECTION_3") (pintype "input"))
    )
    (net (code "18") (name "LMD11") (class "Default")
      (node (ref "CPU1") (pin "82") (pinfunction "RD5_82") (pintype "bidirectional"))
      (node (ref "IC11") (pin "3") (pinfunction "DIRECTION_3") (pintype "input"))
    )
    (net (code "19") (name "LMD12") (class "Default")
      (node (ref "CPU1") (pin "81") (pinfunction "RD4_81") (pintype "bidirectional"))
      (node (ref "IC12") (pin "3") (pinfunction "DIRECTION_3") (pintype "input"))
    )
    (net (code "20") (name "LMD13") (class "Default")
      (node (ref "CPU1") (pin "4") (pinfunction "RE6_4") (pintype "bidirectional"))
      (node (ref "IC13") (pin "3") (pinfunction "DIRECTION_3") (pintype "input"))
    )
    (net (code "21") (name "LMD14") (class "Default")
      (node (ref "CPU1") (pin "5") (pinfunction "RE7_5") (pintype "bidirectional"))
      (node (ref "IC14") (pin "3") (pinfunction "DIRECTION_3") (pintype "input"))
    )
    (net (code "22") (name "MPU_FSYNC") (class "Default")
      (node (ref "CPU1") (pin "61") (pinfunction "RA5_61") (pintype "output"))
      (node (ref "U1") (pin "11") (pinfunction "FSYNC_11") (pintype "bidirectional"))
    )
    (net (code "23") (name "MPU_INT") (class "Default")
      (node (ref "CPU1") (pin "66") (pinfunction "RA14_66") (pintype "bidirectional"))
      (node (ref "U1") (pin "12") (pinfunction "INT_12") (pintype "bidirectional"))
    )
    (net (code "24") (name "MPU_SCL") (class "Default")
      (node (ref "CPU1") (pin "58") (pinfunction "RA2_58") (pintype "bidirectional"))
      (node (ref "R1") (pin "1") (pinfunction "1_1") (pintype "passive"))
      (node (ref "U1") (pin "23") (pinfunction "SCL/SCLK_23") (pintype "bidirectional"))
    )
    (net (code "25") (name "MPU_SDA") (class "Default")
      (node (ref "CPU1") (pin "59") (pinfunction "RA3_59") (pintype "bidirectional"))
      (node (ref "R2") (pin "1") (pinfunction "1_1") (pintype "passive"))
      (node (ref "U1") (pin "24") (pinfunction "SDA/SDI_24") (pintype "bidirectional"))
    )
    (net (code "26") (name "Net-(C3-+)") (class "Default")
      (node (ref "C3") (pin "A") (pinfunction "+_A") (pintype "passive"))
      (node (ref "CPU1") (pin "85") (pinfunction "VCAP_85") (pintype "power_in"))
    )
    (net (code "27") (name "Net-(C55-Pad1)") (class "Default")
      (node (ref "C55") (pin "1") (pinfunction "1_1") (pintype "passive"))
      (node (ref "JP2") (pin "1") (pinfunction "1_1") (pintype "passive"))
    )
    (net (code "28") (name "Net-(IC1-BOOTSTRAP1)") (class "Default")
      (node (ref "C2") (pin "2") (pinfunction "2_2") (pintype "passive"))
      (node (ref "IC1") (pin "1") (pinfunction "BOOTSTRAP1_1") (pintype "input"))
    )
    (net (code "29") (name "Net-(IC1-BOOTSTRAP2)") (class "Default")
      (node (ref "C1") (pin "1") (pinfunction "1_1") (pintype "passive"))
      (node (ref "IC1") (pin "11") (pinfunction "BOOTSTRAP2_11") (pintype "input"))
    )
    (net (code "30") (name "Net-(IC1-OUTPUT1)") (class "Default")
      (node (ref "C2") (pin "1") (pinfunction "1_1") (pintype "passive"))
      (node (ref "IC1") (pin "2") (pinfunction "OUTPUT1_2") (pintype "output"))
      (node (ref "J13") (pin "1") (pinfunction "1_1") (pintype "passive"))
    )
    (net (code "31") (name "Net-(IC1-OUTPUT2)") (class "Default")
      (node (ref "C1") (pin "2") (pinfunction "2_2") (pintype "passive"))
      (node (ref "IC1") (pin "10") (pinfunction "OUTPUT2_10") (pintype "output"))
      (node (ref "J13") (pin "2") (pinfunction "2_2") (pintype "passive"))
    )
    (net (code "32") (name "Net-(IC2-BOOTSTRAP1)") (class "Default")
      (node (ref "C17") (pin "2") (pinfunction "2_2") (pintype "passive"))
      (node (ref "IC2") (pin "1") (pinfunction "BOOTSTRAP1_1") (pintype "input"))
    )
    (net (code "33") (name "Net-(IC2-BOOTSTRAP2)") (class "Default")
      (node (ref "C16") (pin "1") (pinfunction "1_1") (pintype "passive"))
      (node (ref "IC2") (pin "11") (pinfunction "BOOTSTRAP2_11") (pintype "input"))
    )
    (net (code "34") (name "Net-(IC2-OUTPUT1)") (class "Default")
      (node (ref "C17") (pin "1") (pinfunction "1_1") (pintype "passive"))
      (node (ref "IC2") (pin "2") (pinfunction "OUTPUT1_2") (pintype "output"))
      (node (ref "J2") (pin "1") (pinfunction "1_1") (pintype "passive"))
    )
    (net (code "35") (name "Net-(IC2-OUTPUT2)") (class "Default")
      (node (ref "C16") (pin "2") (pinfunction "2_2") (pintype "passive"))
      (node (ref "IC2") (pin "10") (pinfunction "OUTPUT2_10") (pintype "output"))
      (node (ref "J2") (pin "2") (pinfunction "2_2") (pintype "passive"))
    )
    (net (code "36") (name "Net-(IC3-BOOTSTRAP1)") (class "Default")
      (node (ref "C20") (pin "2") (pinfunction "2_2") (pintype "passive"))
      (node (ref "IC3") (pin "1") (pinfunction "BOOTSTRAP1_1") (pintype "input"))
    )
    (net (code "37") (name "Net-(IC3-BOOTSTRAP2)") (class "Default")
      (node (ref "C19") (pin "1") (pinfunction "1_1") (pintype "passive"))
      (node (ref "IC3") (pin "11") (pinfunction "BOOTSTRAP2_11") (pintype "input"))
    )
    (net (code "38") (name "Net-(IC3-OUTPUT1)") (class "Default")
      (node (ref "C20") (pin "1") (pinfunction "1_1") (pintype "passive"))
      (node (ref "IC3") (pin "2") (pinfunction "OUTPUT1_2") (pintype "output"))
      (node (ref "J3") (pin "1") (pinfunction "1_1") (pintype "passive"))
    )
    (net (code "39") (name "Net-(IC3-OUTPUT2)") (class "Default")
      (node (ref "C19") (pin "2") (pinfunction "2_2") (pintype "passive"))
      (node (ref "IC3") (pin "10") (pinfunction "OUTPUT2_10") (pintype "output"))
      (node (ref "J3") (pin "2") (pinfunction "2_2") (pintype "passive"))
    )
    (net (code "40") (name "Net-(IC4-BOOTSTRAP1)") (class "Default")
      (node (ref "C23") (pin "2") (pinfunction "2_2") (pintype "passive"))
      (node (ref "IC4") (pin "1") (pinfunction "BOOTSTRAP1_1") (pintype "input"))
    )
    (net (code "41") (name "Net-(IC4-BOOTSTRAP2)") (class "Default")
      (node (ref "C22") (pin "1") (pinfunction "1_1") (pintype "passive"))
      (node (ref "IC4") (pin "11") (pinfunction "BOOTSTRAP2_11") (pintype "input"))
    )
    (net (code "42") (name "Net-(IC4-OUTPUT1)") (class "Default")
      (node (ref "C23") (pin "1") (pinfunction "1_1") (pintype "passive"))
      (node (ref "IC4") (pin "2") (pinfunction "OUTPUT1_2") (pintype "output"))
      (node (ref "J4") (pin "1") (pinfunction "1_1") (pintype "passive"))
    )
    (net (code "43") (name "Net-(IC4-OUTPUT2)") (class "Default")
      (node (ref "C22") (pin "2") (pinfunction "2_2") (pintype "passive"))
      (node (ref "IC4") (pin "10") (pinfunction "OUTPUT2_10") (pintype "output"))
      (node (ref "J4") (pin "2") (pinfunction "2_2") (pintype "passive"))
    )
    (net (code "44") (name "Net-(IC5-BOOTSTRAP1)") (class "Default")
      (node (ref "C26") (pin "2") (pinfunction "2_2") (pintype "passive"))
      (node (ref "IC5") (pin "1") (pinfunction "BOOTSTRAP1_1") (pintype "input"))
    )
    (net (code "45") (name "Net-(IC5-BOOTSTRAP2)") (class "Default")
      (node (ref "C25") (pin "1") (pinfunction "1_1") (pintype "passive"))
      (node (ref "IC5") (pin "11") (pinfunction "BOOTSTRAP2_11") (pintype "input"))
    )
    (net (code "46") (name "Net-(IC5-OUTPUT1)") (class "Default")
      (node (ref "C26") (pin "1") (pinfunction "1_1") (pintype "passive"))
      (node (ref "IC5") (pin "2") (pinfunction "OUTPUT1_2") (pintype "output"))
      (node (ref "J5") (pin "1") (pinfunction "1_1") (pintype "passive"))
    )
    (net (code "47") (name "Net-(IC5-OUTPUT2)") (class "Default")
      (node (ref "C25") (pin "2") (pinfunction "2_2") (pintype "passive"))
      (node (ref "IC5") (pin "10") (pinfunction "OUTPUT2_10") (pintype "output"))
      (node (ref "J5") (pin "2") (pinfunction "2_2") (pintype "passive"))
    )
    (net (code "48") (name "Net-(IC6-BOOTSTRAP1)") (class "Default")
      (node (ref "C29") (pin "2") (pinfunction "2_2") (pintype "passive"))
      (node (ref "IC6") (pin "1") (pinfunction "BOOTSTRAP1_1") (pintype "input"))
    )
    (net (code "49") (name "Net-(IC6-BOOTSTRAP2)") (class "Default")
      (node (ref "C28") (pin "1") (pinfunction "1_1") (pintype "passive"))
      (node (ref "IC6") (pin "11") (pinfunction "BOOTSTRAP2_11") (pintype "input"))
    )
    (net (code "50") (name "Net-(IC6-OUTPUT1)") (class "Default")
      (node (ref "C29") (pin "1") (pinfunction "1_1") (pintype "passive"))
      (node (ref "IC6") (pin "2") (pinfunction "OUTPUT1_2") (pintype "output"))
      (node (ref "J6") (pin "1") (pinfunction "1_1") (pintype "passive"))
    )
    (net (code "51") (name "Net-(IC6-OUTPUT2)") (class "Default")
      (node (ref "C28") (pin "2") (pinfunction "2_2") (pintype "passive"))
      (node (ref "IC6") (pin "10") (pinfunction "OUTPUT2_10") (pintype "output"))
      (node (ref "J6") (pin "2") (pinfunction "2_2") (pintype "passive"))
    )
    (net (code "52") (name "Net-(IC7-BOOTSTRAP1)") (class "Default")
      (node (ref "C32") (pin "2") (pinfunction "2_2") (pintype "passive"))
      (node (ref "IC7") (pin "1") (pinfunction "BOOTSTRAP1_1") (pintype "input"))
    )
    (net (code "53") (name "Net-(IC7-BOOTSTRAP2)") (class "Default")
      (node (ref "C31") (pin "1") (pinfunction "1_1") (pintype "passive"))
      (node (ref "IC7") (pin "11") (pinfunction "BOOTSTRAP2_11") (pintype "input"))
    )
    (net (code "54") (name "Net-(IC7-OUTPUT1)") (class "Default")
      (node (ref "C32") (pin "1") (pinfunction "1_1") (pintype "passive"))
      (node (ref "IC7") (pin "2") (pinfunction "OUTPUT1_2") (pintype "output"))
      (node (ref "J7") (pin "1") (pinfunction "1_1") (pintype "passive"))
    )
    (net (code "55") (name "Net-(IC7-OUTPUT2)") (class "Default")
      (node (ref "C31") (pin "2") (pinfunction "2_2") (pintype "passive"))
      (node (ref "IC7") (pin "10") (pinfunction "OUTPUT2_10") (pintype "output"))
      (node (ref "J7") (pin "2") (pinfunction "2_2") (pintype "passive"))
    )
    (net (code "56") (name "Net-(IC8-BOOTSTRAP1)") (class "Default")
      (node (ref "C35") (pin "2") (pinfunction "2_2") (pintype "passive"))
      (node (ref "IC8") (pin "1") (pinfunction "BOOTSTRAP1_1") (pintype "input"))
    )
    (net (code "57") (name "Net-(IC8-BOOTSTRAP2)") (class "Default")
      (node (ref "C34") (pin "1") (pinfunction "1_1") (pintype "passive"))
      (node (ref "IC8") (pin "11") (pinfunction "BOOTSTRAP2_11") (pintype "input"))
    )
    (net (code "58") (name "Net-(IC8-OUTPUT1)") (class "Default")
      (node (ref "C35") (pin "1") (pinfunction "1_1") (pintype "passive"))
      (node (ref "IC8") (pin "2") (pinfunction "OUTPUT1_2") (pintype "output"))
      (node (ref "J8") (pin "1") (pinfunction "1_1") (pintype "passive"))
    )
    (net (code "59") (name "Net-(IC8-OUTPUT2)") (class "Default")
      (node (ref "C34") (pin "2") (pinfunction "2_2") (pintype "passive"))
      (node (ref "IC8") (pin "10") (pinfunction "OUTPUT2_10") (pintype "output"))
      (node (ref "J8") (pin "2") (pinfunction "2_2") (pintype "passive"))
    )
    (net (code "60") (name "Net-(IC9-BOOTSTRAP1)") (class "Default")
      (node (ref "C38") (pin "2") (pinfunction "2_2") (pintype "passive"))
      (node (ref "IC9") (pin "1") (pinfunction "BOOTSTRAP1_1") (pintype "input"))
    )
    (net (code "61") (name "Net-(IC9-BOOTSTRAP2)") (class "Default")
      (node (ref "C37") (pin "1") (pinfunction "1_1") (pintype "passive"))
      (node (ref "IC9") (pin "11") (pinfunction "BOOTSTRAP2_11") (pintype "input"))
    )
    (net (code "62") (name "Net-(IC9-OUTPUT1)") (class "Default")
      (node (ref "C38") (pin "1") (pinfunction "1_1") (pintype "passive"))
      (node (ref "IC9") (pin "2") (pinfunction "OUTPUT1_2") (pintype "output"))
      (node (ref "J9") (pin "1") (pinfunction "1_1") (pintype "passive"))
    )
    (net (code "63") (name "Net-(IC9-OUTPUT2)") (class "Default")
      (node (ref "C37") (pin "2") (pinfunction "2_2") (pintype "passive"))
      (node (ref "IC9") (pin "10") (pinfunction "OUTPUT2_10") (pintype "output"))
      (node (ref "J9") (pin "2") (pinfunction "2_2") (pintype "passive"))
    )
    (net (code "64") (name "Net-(IC10-BOOTSTRAP1)") (class "Default")
      (node (ref "C41") (pin "2") (pinfunction "2_2") (pintype "passive"))
      (node (ref "IC10") (pin "1") (pinfunction "BOOTSTRAP1_1") (pintype "input"))
    )
    (net (code "65") (name "Net-(IC10-BOOTSTRAP2)") (class "Default")
      (node (ref "C40") (pin "1") (pinfunction "1_1") (pintype "passive"))
      (node (ref "IC10") (pin "11") (pinfunction "BOOTSTRAP2_11") (pintype "input"))
    )
    (net (code "66") (name "Net-(IC10-OUTPUT1)") (class "Default")
      (node (ref "C41") (pin "1") (pinfunction "1_1") (pintype "passive"))
      (node (ref "IC10") (pin "2") (pinfunction "OUTPUT1_2") (pintype "output"))
      (node (ref "J10") (pin "1") (pinfunction "1_1") (pintype "passive"))
    )
    (net (code "67") (name "Net-(IC10-OUTPUT2)") (class "Default")
      (node (ref "C40") (pin "2") (pinfunction "2_2") (pintype "passive"))
      (node (ref "IC10") (pin "10") (pinfunction "OUTPUT2_10") (pintype "output"))
      (node (ref "J10") (pin "2") (pinfunction "2_2") (pintype "passive"))
    )
    (net (code "68") (name "Net-(IC11-BOOTSTRAP1)") (class "Default")
      (node (ref "C44") (pin "2") (pinfunction "2_2") (pintype "passive"))
      (node (ref "IC11") (pin "1") (pinfunction "BOOTSTRAP1_1") (pintype "input"))
    )
    (net (code "69") (name "Net-(IC11-BOOTSTRAP2)") (class "Default")
      (node (ref "C43") (pin "1") (pinfunction "1_1") (pintype "passive"))
      (node (ref "IC11") (pin "11") (pinfunction "BOOTSTRAP2_11") (pintype "input"))
    )
    (net (code "70") (name "Net-(IC11-OUTPUT1)") (class "Default")
      (node (ref "C44") (pin "1") (pinfunction "1_1") (pintype "passive"))
      (node (ref "IC11") (pin "2") (pinfunction "OUTPUT1_2") (pintype "output"))
      (node (ref "J11") (pin "1") (pinfunction "1_1") (pintype "passive"))
    )
    (net (code "71") (name "Net-(IC11-OUTPUT2)") (class "Default")
      (node (ref "C43") (pin "2") (pinfunction "2_2") (pintype "passive"))
      (node (ref "IC11") (pin "10") (pinfunction "OUTPUT2_10") (pintype "output"))
      (node (ref "J11") (pin "2") (pinfunction "2_2") (pintype "passive"))
    )
    (net (code "72") (name "Net-(IC12-BOOTSTRAP1)") (class "Default")
      (node (ref "C47") (pin "2") (pinfunction "2_2") (pintype "passive"))
      (node (ref "IC12") (pin "1") (pinfunction "BOOTSTRAP1_1") (pintype "input"))
    )
    (net (code "73") (name "Net-(IC12-BOOTSTRAP2)") (class "Default")
      (node (ref "C46") (pin "1") (pinfunction "1_1") (pintype "passive"))
      (node (ref "IC12") (pin "11") (pinfunction "BOOTSTRAP2_11") (pintype "input"))
    )
    (net (code "74") (name "Net-(IC12-OUTPUT1)") (class "Default")
      (node (ref "C47") (pin "1") (pinfunction "1_1") (pintype "passive"))
      (node (ref "IC12") (pin "2") (pinfunction "OUTPUT1_2") (pintype "output"))
      (node (ref "J14") (pin "1") (pinfunction "1_1") (pintype "passive"))
    )
    (net (code "75") (name "Net-(IC12-OUTPUT2)") (class "Default")
      (node (ref "C46") (pin "2") (pinfunction "2_2") (pintype "passive"))
      (node (ref "IC12") (pin "10") (pinfunction "OUTPUT2_10") (pintype "output"))
      (node (ref "J14") (pin "2") (pinfunction "2_2") (pintype "passive"))
    )
    (net (code "76") (name "Net-(IC13-BOOTSTRAP1)") (class "Default")
      (node (ref "C50") (pin "2") (pinfunction "2_2") (pintype "passive"))
      (node (ref "IC13") (pin "1") (pinfunction "BOOTSTRAP1_1") (pintype "input"))
    )
    (net (code "77") (name "Net-(IC13-BOOTSTRAP2)") (class "Default")
      (node (ref "C49") (pin "1") (pinfunction "1_1") (pintype "passive"))
      (node (ref "IC13") (pin "11") (pinfunction "BOOTSTRAP2_11") (pintype "input"))
    )
    (net (code "78") (name "Net-(IC13-OUTPUT1)") (class "Default")
      (node (ref "C50") (pin "1") (pinfunction "1_1") (pintype "passive"))
      (node (ref "IC13") (pin "2") (pinfunction "OUTPUT1_2") (pintype "output"))
      (node (ref "J15") (pin "1") (pinfunction "1_1") (pintype "passive"))
    )
    (net (code "79") (name "Net-(IC13-OUTPUT2)") (class "Default")
      (node (ref "C49") (pin "2") (pinfunction "2_2") (pintype "passive"))
      (node (ref "IC13") (pin "10") (pinfunction "OUTPUT2_10") (pintype "output"))
      (node (ref "J15") (pin "2") (pinfunction "2_2") (pintype "passive"))
    )
    (net (code "80") (name "Net-(IC14-BOOTSTRAP1)") (class "Default")
      (node (ref "C53") (pin "2") (pinfunction "2_2") (pintype "passive"))
      (node (ref "IC14") (pin "1") (pinfunction "BOOTSTRAP1_1") (pintype "input"))
    )
    (net (code "81") (name "Net-(IC14-BOOTSTRAP2)") (class "Default")
      (node (ref "C52") (pin "1") (pinfunction "1_1") (pintype "passive"))
      (node (ref "IC14") (pin "11") (pinfunction "BOOTSTRAP2_11") (pintype "input"))
    )
    (net (code "82") (name "Net-(IC14-OUTPUT1)") (class "Default")
      (node (ref "C53") (pin "1") (pinfunction "1_1") (pintype "passive"))
      (node (ref "IC14") (pin "2") (pinfunction "OUTPUT1_2") (pintype "output"))
      (node (ref "J16") (pin "1") (pinfunction "1_1") (pintype "passive"))
    )
    (net (code "83") (name "Net-(IC14-OUTPUT2)") (class "Default")
      (node (ref "C52") (pin "2") (pinfunction "2_2") (pintype "passive"))
      (node (ref "IC14") (pin "10") (pinfunction "OUTPUT2_10") (pintype "output"))
      (node (ref "J16") (pin "2") (pinfunction "2_2") (pintype "passive"))
    )
    (net (code "84") (name "Net-(JP2-Pad2)") (class "Default")
      (node (ref "JP2") (pin "2") (pinfunction "2_2") (pintype "passive"))
      (node (ref "R7") (pin "1") (pinfunction "1_1") (pintype "passive"))
      (node (ref "R8") (pin "2") (pinfunction "2_2") (pintype "passive"))
    )
    (net (code "85") (name "Net-(U$17-EN)") (class "Default")
      (node (ref "R15") (pin "1") (pinfunction "1_1") (pintype "passive"))
      (node (ref "U$17") (pin "7") (pinfunction "VREF2_7") (pintype "bidirectional"))
      (node (ref "U$17") (pin "8") (pinfunction "EN_8") (pintype "bidirectional"))
    )
    (net (code "86") (name "Net-(U$17-SCL1)") (class "Default")
      (node (ref "R14") (pin "1") (pinfunction "1_1") (pintype "passive"))
      (node (ref "SV1") (pin "3") (pinfunction "3_3") (pintype "passive"))
      (node (ref "U$17") (pin "2") (pinfunction "SCL1_2") (pintype "bidirectional"))
    )
    (net (code "87") (name "Net-(U$17-SDA1)") (class "Default")
      (node (ref "R13") (pin "1") (pinfunction "1_1") (pintype "passive"))
      (node (ref "SV1") (pin "2") (pinfunction "2_2") (pintype "passive"))
      (node (ref "U$17") (pin "3") (pinfunction "SDA1_3") (pintype "bidirectional"))
    )
    (net (code "88") (name "Net-(U$17-VREF1)") (class "Default")
      (node (ref "R13") (pin "2") (pinfunction "2_2") (pintype "passive"))
      (node (ref "R14") (pin "2") (pinfunction "2_2") (pintype "passive"))
      (node (ref "SV1") (pin "4") (pinfunction "4_4") (pintype "passive"))
      (node (ref "U$17") (pin "1") (pinfunction "VREF1_1") (pintype "bidirectional"))
    )
    (net (code "89") (name "Net-(U1-CPOUT)") (class "Default")
      (node (ref "C14") (pin "1") (pinfunction "1_1") (pintype "passive"))
      (node (ref "U1") (pin "20") (pinfunction "CPOUT_20") (pintype "bidirectional"))
    )
    (net (code "90") (name "Net-(U1-REGOUT)") (class "Default")
      (node (ref "C13") (pin "1") (pinfunction "1_1") (pintype "passive"))
      (node (ref "U1") (pin "10") (pinfunction "REGOUT_10") (pintype "bidirectional"))
    )
    (net (code "91") (name "PROG_4") (class "Default")
      (node (ref "CPU1") (pin "27") (pinfunction "RB7_27") (pintype "bidirectional"))
      (node (ref "JP1") (pin "4") (pinfunction "4_4") (pintype "passive"))
    )
    (net (code "92") (name "PROG_5") (class "Default")
      (node (ref "CPU1") (pin "26") (pinfunction "RB6_26") (pintype "bidirectional"))
      (node (ref "JP1") (pin "5") (pinfunction "5_5") (pintype "passive"))
    )
    (net (code "93") (name "TH_LMD1") (class "Default")
      (node (ref "CPU1") (pin "12") (pinfunction "RG8_12") (pintype "bidirectional"))
      (node (ref "IC1") (pin "9") (pinfunction "THERMAL_9") (pintype "output"))
    )
    (net (code "94") (name "TH_LMD2") (class "Default")
      (node (ref "CPU1") (pin "14") (pinfunction "RG9_14") (pintype "bidirectional"))
      (node (ref "IC2") (pin "9") (pinfunction "THERMAL_9") (pintype "output"))
    )
    (net (code "95") (name "TH_LMD3") (class "Default")
      (node (ref "CPU1") (pin "8") (pinfunction "RC3_8") (pintype "bidirectional"))
      (node (ref "IC5") (pin "9") (pinfunction "THERMAL_9") (pintype "output"))
    )
    (net (code "96") (name "TH_LMD4") (class "Default")
      (node (ref "CPU1") (pin "9") (pinfunction "RC4_9") (pintype "bidirectional"))
      (node (ref "IC6") (pin "9") (pinfunction "THERMAL_9") (pintype "output"))
    )
    (net (code "97") (name "TH_LMD5") (class "Default")
      (node (ref "CPU1") (pin "10") (pinfunction "RG6_10") (pintype "bidirectional"))
      (node (ref "IC3") (pin "9") (pinfunction "THERMAL_9") (pintype "output"))
    )
    (net (code "98") (name "TH_LMD6") (class "Default")
      (node (ref "CPU1") (pin "11") (pinfunction "RG7_11") (pintype "bidirectional"))
      (node (ref "IC4") (pin "9") (pinfunction "THERMAL_9") (pintype "output"))
    )
    (net (code "99") (name "TH_LMD7") (class "Default")
      (node (ref "CPU1") (pin "6") (pinfunction "RC1_6") (pintype "bidirectional"))
      (node (ref "IC7") (pin "9") (pinfunction "THERMAL_9") (pintype "output"))
    )
    (net (code "100") (name "TH_LMD8") (class "Default")
      (node (ref "CPU1") (pin "7") (pinfunction "RC2_7") (pintype "bidirectional"))
      (node (ref "IC8") (pin "9") (pinfunction "THERMAL_9") (pintype "output"))
    )
    (net (code "101") (name "TH_LMD9") (class "Default")
      (node (ref "CPU1") (pin "90") (pinfunction "RG0_90") (pintype "bidirectional"))
      (node (ref "IC9") (pin "9") (pinfunction "THERMAL_9") (pintype "output"))
    )
    (net (code "102") (name "TH_LMD10") (class "Default")
      (node (ref "CPU1") (pin "89") (pinfunction "RG1_89") (pintype "bidirectional"))
      (node (ref "IC10") (pin "9") (pinfunction "THERMAL_9") (pintype "output"))
    )
    (net (code "103") (name "TH_LMD11") (class "Default")
      (node (ref "CPU1") (pin "88") (pinfunction "RF1_88") (pintype "bidirectional"))
      (node (ref "IC11") (pin "9") (pinfunction "THERMAL_9") (pintype "output"))
    )
    (net (code "104") (name "TH_LMD12") (class "Default")
      (node (ref "CPU1") (pin "87") (pinfunction "RF0_87") (pintype "bidirectional"))
      (node (ref "IC12") (pin "9") (pinfunction "THERMAL_9") (pintype "output"))
    )
    (net (code "105") (name "TH_LMD13") (class "Default")
      (node (ref "CPU1") (pin "21") (pinfunction "RB4_21") (pintype "bidirectional"))
      (node (ref "IC13") (pin "9") (pinfunction "THERMAL_9") (pintype "output"))
    )
    (net (code "106") (name "TH_LMD14") (class "Default")
      (node (ref "CPU1") (pin "22") (pinfunction "RB3_22") (pintype "bidirectional"))
      (node (ref "IC14") (pin "9") (pinfunction "THERMAL_9") (pintype "output"))
    )
    (net (code "107") (name "TRANSFORMER_IN") (class "Default")
      (node (ref "J19") (pin "2") (pinfunction "2_2") (pintype "passive"))
      (node (ref "R9") (pin "1") (pinfunction "1_1") (pintype "passive"))
    )
    (net (code "108") (name "TRANS_OUT_MON") (class "Default")
      (node (ref "CPU1") (pin "42") (pinfunction "RB13_42") (pintype "bidirectional"))
      (node (ref "R10") (pin "2") (pinfunction "2_2") (pintype "passive"))
      (node (ref "R9") (pin "2") (pinfunction "2_2") (pintype "passive"))
    )
    (net (code "109") (name "VCC") (class "Default")
      (node (ref "C7") (pin "1") (pinfunction "1_1") (pintype "passive"))
      (node (ref "CPU1") (pin "30") (pinfunction "AVDD_30") (pintype "power_in"))
      (node (ref "I1") (pin "P$2") (pinfunction "2_P$2") (pintype "passive"))
    )
    (net (code "110") (name "VDD") (class "Default")
      (node (ref "C10") (pin "1") (pinfunction "1_1") (pintype "passive"))
      (node (ref "C12") (pin "1") (pinfunction "1_1") (pintype "passive"))
      (node (ref "C15") (pin "1") (pinfunction "1_1") (pintype "passive"))
      (node (ref "C4") (pin "1") (pinfunction "1_1") (pintype "passive"))
      (node (ref "C5") (pin "1") (pinfunction "1_1") (pintype "passive"))
      (node (ref "C6") (pin "1") (pinfunction "1_1") (pintype "passive"))
      (node (ref "C8") (pin "1") (pinfunction "1_1") (pintype "passive"))
      (node (ref "C9") (pin "1") (pinfunction "1_1") (pintype "passive"))
      (node (ref "CPU1") (pin "16") (pinfunction "VDD2_16") (pintype "power_in"))
      (node (ref "CPU1") (pin "2") (pinfunction "VDD1_2") (pintype "power_in"))
      (node (ref "CPU1") (pin "37") (pinfunction "VDD3_37") (pintype "power_in"))
      (node (ref "CPU1") (pin "46") (pinfunction "VDD4_46") (pintype "power_in"))
      (node (ref "CPU1") (pin "62") (pinfunction "VDD5_62") (pintype "power_in"))
      (node (ref "CPU1") (pin "86") (pinfunction "VDD_86") (pintype "passive"))
      (node (ref "I1") (pin "P$1") (pinfunction "1_P$1") (pintype "passive"))
      (node (ref "IC1") (pin "5") (pinfunction "PWM_5") (pintype "input"))
      (node (ref "IC10") (pin "5") (pinfunction "PWM_5") (pintype "input"))
      (node (ref "IC11") (pin "5") (pinfunction "PWM_5") (pintype "input"))
      (node (ref "IC12") (pin "5") (pinfunction "PWM_5") (pintype "input"))
      (node (ref "IC13") (pin "5") (pinfunction "PWM_5") (pintype "input"))
      (node (ref "IC14") (pin "5") (pinfunction "PWM_5") (pintype "input"))
      (node (ref "IC2") (pin "5") (pinfunction "PWM_5") (pintype "input"))
      (node (ref "IC3") (pin "5") (pinfunction "PWM_5") (pintype "input"))
      (node (ref "IC4") (pin "5") (pinfunction "PWM_5") (pintype "input"))
      (node (ref "IC5") (pin "5") (pinfunction "PWM_5") (pintype "input"))
      (node (ref "IC6") (pin "5") (pinfunction "PWM_5") (pintype "input"))
      (node (ref "IC7") (pin "5") (pinfunction "PWM_5") (pintype "input"))
      (node (ref "IC8") (pin "5") (pinfunction "PWM_5") (pintype "input"))
      (node (ref "IC9") (pin "5") (pinfunction "PWM_5") (pintype "input"))
      (node (ref "J1") (pin "2") (pinfunction "2_2") (pintype "passive"))
      (node (ref "JP1") (pin "2") (pinfunction "2_2") (pintype "passive"))
      (node (ref "R1") (pin "2") (pinfunction "2_2") (pintype "passive"))
      (node (ref "R11") (pin "2") (pinfunction "2_2") (pintype "passive"))
      (node (ref "R12") (pin "2") (pinfunction "2_2") (pintype "passive"))
      (node (ref "R15") (pin "2") (pinfunction "2_2") (pintype "passive"))
      (node (ref "R2") (pin "2") (pinfunction "2_2") (pintype "passive"))
      (node (ref "R7") (pin "2") (pinfunction "2_2") (pintype "passive"))
      (node (ref "U1") (pin "13") (pinfunction "VDD_13") (pintype "bidirectional"))
      (node (ref "U1") (pin "8") (pinfunction "CS_8") (pintype "bidirectional"))
    )
    (net (code "111") (name "unconnected-(CPU1-RA0-Pad17)") (class "Default")
      (node (ref "CPU1") (pin "17") (pinfunction "RA0_17") (pintype "input"))
    )
    (net (code "112") (name "unconnected-(CPU1-RA1-Pad38)") (class "Default")
      (node (ref "CPU1") (pin "38") (pinfunction "RA1_38") (pintype "input"))
    )
    (net (code "113") (name "unconnected-(CPU1-RA4-Pad60)") (class "Default")
      (node (ref "CPU1") (pin "60") (pinfunction "RA4_60") (pintype "input"))
    )
    (net (code "114") (name "unconnected-(CPU1-RA6-Pad91)") (class "Default")
      (node (ref "CPU1") (pin "91") (pinfunction "RA6_91") (pintype "bidirectional"))
    )
    (net (code "115") (name "unconnected-(CPU1-RA9-Pad28)") (class "Default")
      (node (ref "CPU1") (pin "28") (pinfunction "RA9_28") (pintype "bidirectional"))
    )
    (net (code "116") (name "unconnected-(CPU1-RA10-Pad29)") (class "Default")
      (node (ref "CPU1") (pin "29") (pinfunction "RA10_29") (pintype "bidirectional"))
    )
    (net (code "117") (name "unconnected-(CPU1-RA15-Pad67)") (class "Default")
      (node (ref "CPU1") (pin "67") (pinfunction "RA15_67") (pintype "bidirectional"))
    )
    (net (code "118") (name "unconnected-(CPU1-RB0-Pad25)") (class "Default")
      (node (ref "CPU1") (pin "25") (pinfunction "RB0_25") (pintype "bidirectional"))
    )
    (net (code "119") (name "unconnected-(CPU1-RB1-Pad24)") (class "Default")
      (node (ref "CPU1") (pin "24") (pinfunction "RB1_24") (pintype "bidirectional"))
    )
    (net (code "120") (name "unconnected-(CPU1-RB2-Pad23)") (class "Default")
      (node (ref "CPU1") (pin "23") (pinfunction "RB2_23") (pintype "bidirectional"))
    )
    (net (code "121") (name "unconnected-(CPU1-RB5-Pad20)") (class "Default")
      (node (ref "CPU1") (pin "20") (pinfunction "RB5_20") (pintype "bidirectional"))
    )
    (net (code "122") (name "unconnected-(CPU1-RB8-Pad32)") (class "Default")
      (node (ref "CPU1") (pin "32") (pinfunction "RB8_32") (pintype "bidirectional"))
    )
    (net (code "123") (name "unconnected-(CPU1-RB9-Pad33)") (class "Default")
      (node (ref "CPU1") (pin "33") (pinfunction "RB9_33") (pintype "bidirectional"))
    )
    (net (code "124") (name "unconnected-(CPU1-RB10-Pad34)") (class "Default")
      (node (ref "CPU1") (pin "34") (pinfunction "RB10_34") (pintype "bidirectional"))
    )
    (net (code "125") (name "unconnected-(CPU1-RB11-Pad35)") (class "Default")
      (node (ref "CPU1") (pin "35") (pinfunction "RB11_35") (pintype "bidirectional"))
    )
    (net (code "126") (name "unconnected-(CPU1-RB12-Pad41)") (class "Default")
      (node (ref "CPU1") (pin "41") (pinfunction "RB12_41") (pintype "bidirectional"))
    )
    (net (code "127") (name "unconnected-(CPU1-RB14-Pad43)") (class "Default")
      (node (ref "CPU1") (pin "43") (pinfunction "RB14_43") (pintype "bidirectional"))
    )
    (net (code "128") (name "unconnected-(CPU1-RB15-Pad44)") (class "Default")
      (node (ref "CPU1") (pin "44") (pinfunction "RB15_44") (pintype "bidirectional"))
    )
    (net (code "129") (name "unconnected-(CPU1-RC12-Pad63)") (class "Default")
      (node (ref "CPU1") (pin "63") (pinfunction "RC12_63") (pintype "bidirectional"))
    )
    (net (code "130") (name "unconnected-(CPU1-RC13-Pad73)") (class "Default")
      (node (ref "CPU1") (pin "73") (pinfunction "RC13_73") (pintype "bidirectional"))
    )
    (net (code "131") (name "unconnected-(CPU1-RC14-Pad74)") (class "Default")
      (node (ref "CPU1") (pin "74") (pinfunction "RC14_74") (pintype "bidirectional"))
    )
    (net (code "132") (name "unconnected-(CPU1-RC15-Pad64)") (class "Default")
      (node (ref "CPU1") (pin "64") (pinfunction "RC15_64") (pintype "bidirectional"))
    )
    (net (code "133") (name "unconnected-(CPU1-RD0-Pad72)") (class "Default")
      (node (ref "CPU1") (pin "72") (pinfunction "RD0_72") (pintype "bidirectional"))
    )
    (net (code "134") (name "unconnected-(CPU1-RD1-Pad76)") (class "Default")
      (node (ref "CPU1") (pin "76") (pinfunction "RD1_76") (pintype "bidirectional"))
    )
    (net (code "135") (name "unconnected-(CPU1-RD2-Pad77)") (class "Default")
      (node (ref "CPU1") (pin "77") (pinfunction "RD2_77") (pintype "bidirectional"))
    )
    (net (code "136") (name "unconnected-(CPU1-RD3-Pad78)") (class "Default")
      (node (ref "CPU1") (pin "78") (pinfunction "RD3_78") (pintype "bidirectional"))
    )
    (net (code "137") (name "unconnected-(CPU1-RD8-Pad68)") (class "Default")
      (node (ref "CPU1") (pin "68") (pinfunction "RD8_68") (pintype "bidirectional"))
    )
    (net (code "138") (name "unconnected-(CPU1-RD9-Pad69)") (class "Default")
      (node (ref "CPU1") (pin "69") (pinfunction "RD9_69") (pintype "bidirectional"))
    )
    (net (code "139") (name "unconnected-(CPU1-RD10-Pad70)") (class "Default")
      (node (ref "CPU1") (pin "70") (pinfunction "RD10_70") (pintype "bidirectional"))
    )
    (net (code "140") (name "unconnected-(CPU1-RD11-Pad71)") (class "Default")
      (node (ref "CPU1") (pin "71") (pinfunction "RD11_71") (pintype "bidirectional"))
    )
    (net (code "141") (name "unconnected-(CPU1-RD12-Pad79)") (class "Default")
      (node (ref "CPU1") (pin "79") (pinfunction "RD12_79") (pintype "bidirectional"))
    )
    (net (code "142") (name "unconnected-(CPU1-RD13-Pad80)") (class "Default")
      (node (ref "CPU1") (pin "80") (pinfunction "RD13_80") (pintype "bidirectional"))
    )
    (net (code "143") (name "unconnected-(CPU1-RD14-Pad47)") (class "Default")
      (node (ref "CPU1") (pin "47") (pinfunction "RD14_47") (pintype "bidirectional"))
    )
    (net (code "144") (name "unconnected-(CPU1-RD15-Pad48)") (class "Default")
      (node (ref "CPU1") (pin "48") (pinfunction "RD15_48") (pintype "bidirectional"))
    )
    (net (code "145") (name "unconnected-(CPU1-RE8-Pad18)") (class "Default")
      (node (ref "CPU1") (pin "18") (pinfunction "RE8_18") (pintype "bidirectional"))
    )
    (net (code "146") (name "unconnected-(CPU1-RE9-Pad19)") (class "Default")
      (node (ref "CPU1") (pin "19") (pinfunction "RE9_19") (pintype "bidirectional"))
    )
    (net (code "147") (name "unconnected-(CPU1-RF2-Pad52)") (class "Default")
      (node (ref "CPU1") (pin "52") (pinfunction "RF2_52") (pintype "bidirectional"))
    )
    (net (code "148") (name "unconnected-(CPU1-RF3-Pad51)") (class "Default")
      (node (ref "CPU1") (pin "51") (pinfunction "RF3_51") (pintype "bidirectional"))
    )
    (net (code "149") (name "unconnected-(CPU1-RF4-Pad49)") (class "Default")
      (node (ref "CPU1") (pin "49") (pinfunction "RF4_49") (pintype "bidirectional"))
    )
    (net (code "150") (name "unconnected-(CPU1-RF5-Pad50)") (class "Default")
      (node (ref "CPU1") (pin "50") (pinfunction "RF5_50") (pintype "bidirectional"))
    )
    (net (code "151") (name "unconnected-(CPU1-RF6-Pad55)") (class "Default")
      (node (ref "CPU1") (pin "55") (pinfunction "RF6_55") (pintype "bidirectional"))
    )
    (net (code "152") (name "unconnected-(CPU1-RF7-Pad54)") (class "Default")
      (node (ref "CPU1") (pin "54") (pinfunction "RF7_54") (pintype "bidirectional"))
    )
    (net (code "153") (name "unconnected-(CPU1-RF8-Pad53)") (class "Default")
      (node (ref "CPU1") (pin "53") (pinfunction "RF8_53") (pintype "bidirectional"))
    )
    (net (code "154") (name "unconnected-(CPU1-RF13-Pad39)") (class "Default")
      (node (ref "CPU1") (pin "39") (pinfunction "RF13_39") (pintype "bidirectional"))
    )
    (net (code "155") (name "unconnected-(CPU1-RG14-Pad95)") (class "Default")
      (node (ref "CPU1") (pin "95") (pinfunction "RG14_95") (pintype "bidirectional"))
    )
    (net (code "156") (name "unconnected-(CPU1-RG15-Pad1)") (class "Default")
      (node (ref "CPU1") (pin "1") (pinfunction "RG15_1") (pintype "bidirectional"))
    )
    (net (code "157") (name "unconnected-(U1-AUXCL-Pad7)") (class "Default")
      (node (ref "U1") (pin "7") (pinfunction "AUXCL_7") (pintype "bidirectional"))
    )
    (net (code "158") (name "unconnected-(U1-AUXDA-Pad6)") (class "Default")
      (node (ref "U1") (pin "6") (pinfunction "AUXDA_6") (pintype "bidirectional"))
    )
    (net (code "159") (name "unconnected-(U1-CLKOUT-Pad22)") (class "Default")
      (node (ref "U1") (pin "22") (pinfunction "CLKOUT_22") (pintype "bidirectional"))
    )
    (net (code "160") (name "~{MCLR}") (class "Default")
      (node (ref "CPU1") (pin "13") (pinfunction "~{MCLR}_13") (pintype "bidirectional"))
      (node (ref "JP1") (pin "1") (pinfunction "1_1") (pintype "passive"))
      (node (ref "R8") (pin "1") (pinfunction "1_1") (pintype "passive"))
    )
  )
)
